# io-board-b-3.net
KiCad netlist of a schematic drawn in EAGLE
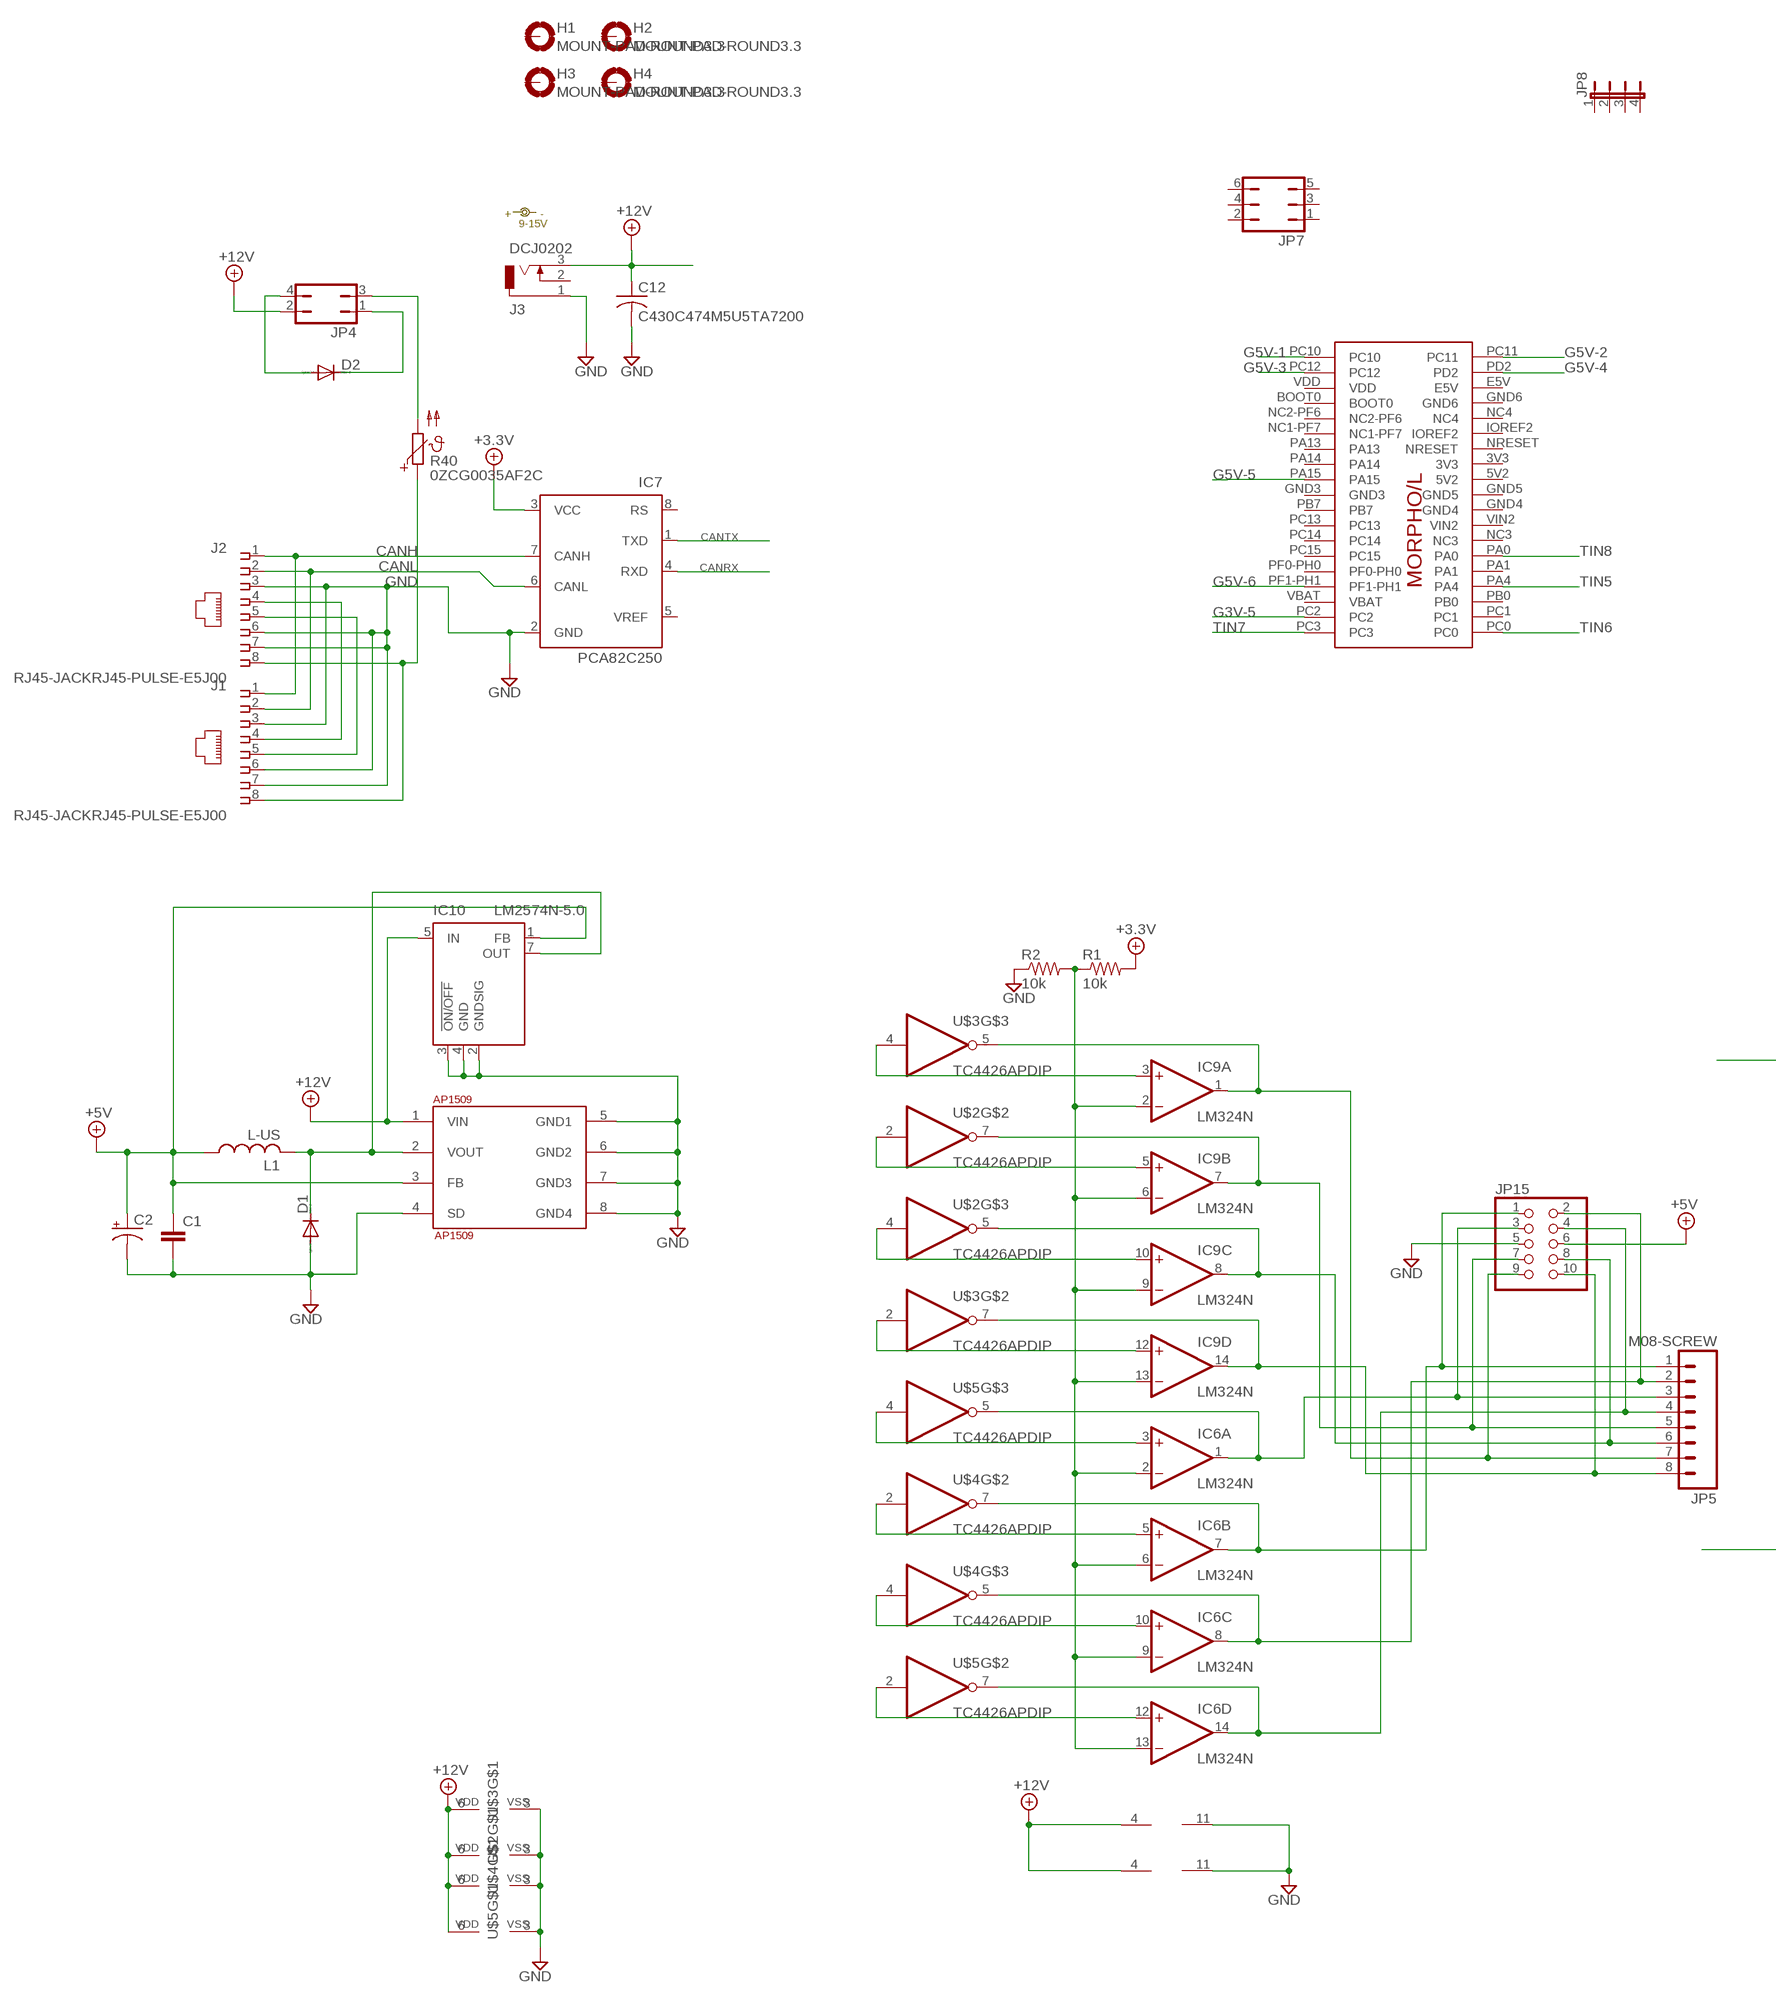
[diagram p0: schematic, sheet 1, part 1 of 2]
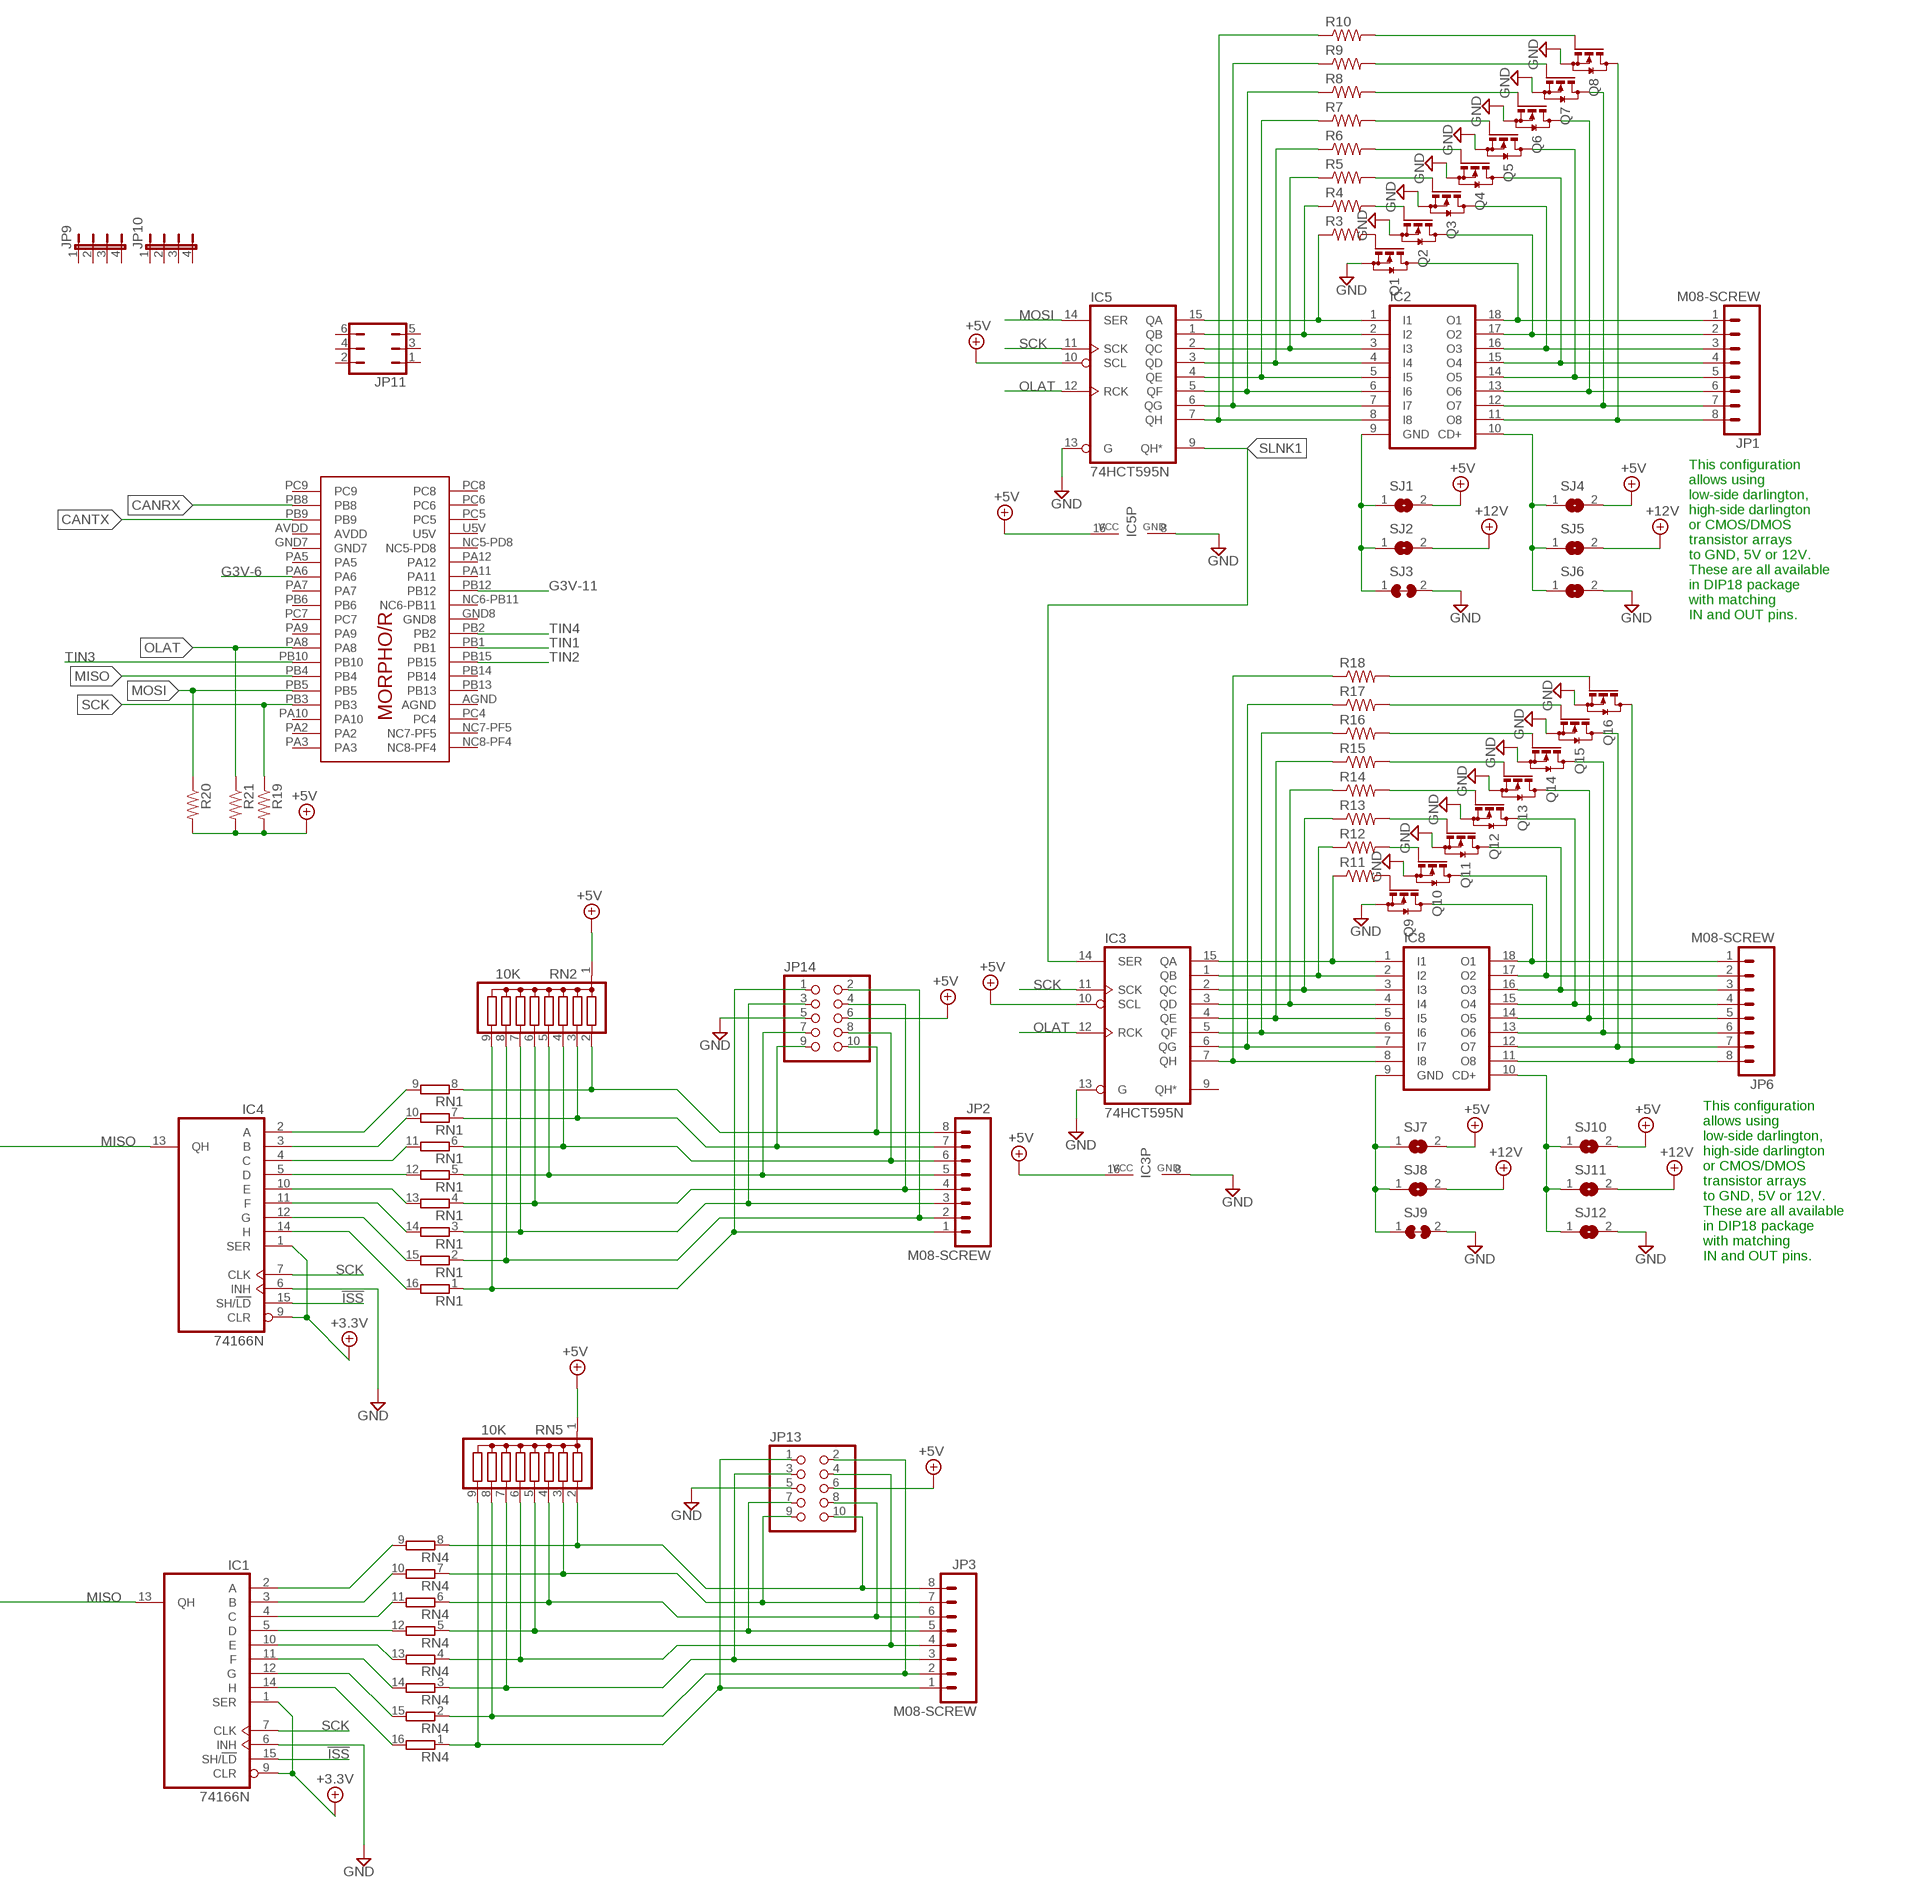
[diagram p1: schematic, sheet 1, part 2 of 2]

(export (version "E")
  (design (tool "Eeschema 10.0.6"))
  (components
    (comp (ref "+12V")
      (value "9-15V")
      (footprint "eagle-import:POWER_USAGE")
      (libsource (lib "eagle-import") (part "DOC-POWER_LABEL"))
    )
    (comp (ref "AP1509")
      (value "AP1509")
      (footprint "eagle-import:SO-08")
      (libsource (lib "eagle-import") (part "AP1509"))
    )
    (comp (ref "C1")
      (value "C-EUC1206")
      (footprint "eagle-import:C1206")
      (libsource (lib "eagle-import") (part "C-EUC1206"))
    )
    (comp (ref "C2")
      (value "CPOL-USE2.5-5")
      (footprint "eagle-import:E2,5-5")
      (libsource (lib "eagle-import") (part "CPOL-USE2.5-5"))
    )
    (comp (ref "C12")
      (value "C430C474M5U5TA7200")
      (footprint "eagle-import:C075-032X103")
      (libsource (lib "eagle-import") (part "C-US075-032X103"))
    )
    (comp (ref "D1")
      (value "DIODE-DO41-7.6")
      (footprint "eagle-import:DO41-7.6")
      (libsource (lib "eagle-import") (part "DIODE-DO41-7.6"))
    )
    (comp (ref "D2")
      (value "DIODE-DO41-7.6")
      (footprint "eagle-import:DO41-7.6")
      (libsource (lib "eagle-import") (part "DIODE-DO41-7.6"))
    )
    (comp (ref "H1")
      (value "MOUNT-PAD-ROUND3.3")
      (footprint "eagle-import:3,3-PAD")
      (libsource (lib "eagle-import") (part "MOUNT-PAD-ROUND3.3"))
    )
    (comp (ref "H2")
      (value "MOUNT-PAD-ROUND3.3")
      (footprint "eagle-import:3,3-PAD")
      (libsource (lib "eagle-import") (part "MOUNT-PAD-ROUND3.3"))
    )
    (comp (ref "H3")
      (value "MOUNT-PAD-ROUND3.3")
      (footprint "eagle-import:3,3-PAD")
      (libsource (lib "eagle-import") (part "MOUNT-PAD-ROUND3.3"))
    )
    (comp (ref "H4")
      (value "MOUNT-PAD-ROUND3.3")
      (footprint "eagle-import:3,3-PAD")
      (libsource (lib "eagle-import") (part "MOUNT-PAD-ROUND3.3"))
    )
    (comp (ref "IC1")
      (value "74166N")
      (footprint "eagle-import:DIL16")
      (libsource (lib "eagle-import") (part "74166N"))
    )
    (comp (ref "IC2")
      (value "ULN2803A")
      (footprint "eagle-import:DIL18-THIN")
      (libsource (lib "eagle-import") (part "ULN2803A"))
    )
    (comp (ref "IC3")
      (value "74HCT595N")
      (footprint "eagle-import:DIL16")
      (libsource (lib "eagle-import") (part "74595NHCT"))
    )
    (comp (ref "IC4")
      (value "74166N")
      (footprint "eagle-import:DIL16")
      (libsource (lib "eagle-import") (part "74166N"))
    )
    (comp (ref "IC5")
      (value "74HCT595N")
      (footprint "eagle-import:DIL16")
      (libsource (lib "eagle-import") (part "74595NHCT"))
    )
    (comp (ref "IC6")
      (value "LM324N")
      (footprint "eagle-import:DIL14")
      (libsource (lib "eagle-import") (part "LM324N"))
    )
    (comp (ref "IC7")
      (value "PCA82C250")
      (footprint "eagle-import:DIL08")
      (libsource (lib "eagle-import") (part "PCA82C250"))
    )
    (comp (ref "IC8")
      (value "ULN2803A")
      (footprint "eagle-import:DIL18-THIN")
      (libsource (lib "eagle-import") (part "ULN2803A"))
    )
    (comp (ref "IC9")
      (value "LM324N")
      (footprint "eagle-import:DIL14")
      (libsource (lib "eagle-import") (part "LM324N"))
    )
    (comp (ref "IC10")
      (value "LM2574N-5.0")
      (footprint "eagle-import:DIL08")
      (libsource (lib "eagle-import") (part "LM2574?-N5.0"))
    )
    (comp (ref "J1")
      (value "RJ45-JACKRJ45-PULSE-E5J00")
      (footprint "eagle-import:RJ45-PULSE-E5J88")
      (libsource (lib "eagle-import") (part "RJ45-JACKRJ45-PULSE-E5J00"))
    )
    (comp (ref "J2")
      (value "RJ45-JACKRJ45-PULSE-E5J00")
      (footprint "eagle-import:RJ45-PULSE-E5J88")
      (libsource (lib "eagle-import") (part "RJ45-JACKRJ45-PULSE-E5J00"))
    )
    (comp (ref "J3")
      (value "DCJ0202")
      (footprint "eagle-import:DCJ0202")
      (libsource (lib "eagle-import") (part "DCJ0202"))
    )
    (comp (ref "JP1")
      (value "M08-SCREW")
      (footprint "eagle-import:1X08_TERMINAL")
      (libsource (lib "eagle-import") (part "M08-SCREW"))
    )
    (comp (ref "JP2")
      (value "M08-SCREW")
      (footprint "eagle-import:1X08_TERMINAL")
      (libsource (lib "eagle-import") (part "M08-SCREW"))
    )
    (comp (ref "JP3")
      (value "M08-SCREW")
      (footprint "eagle-import:1X08_TERMINAL")
      (libsource (lib "eagle-import") (part "M08-SCREW"))
    )
    (comp (ref "JP4")
      (value "JP2Q")
      (footprint "eagle-import:JP2Q")
      (libsource (lib "eagle-import") (part "JP2Q"))
    )
    (comp (ref "JP5")
      (value "M08-SCREW")
      (footprint "eagle-import:1X08_TERMINAL")
      (libsource (lib "eagle-import") (part "M08-SCREW"))
    )
    (comp (ref "JP6")
      (value "M08-SCREW")
      (footprint "eagle-import:1X08_TERMINAL")
      (libsource (lib "eagle-import") (part "M08-SCREW"))
    )
    (comp (ref "JP7")
      (value "JP3Q")
      (footprint "eagle-import:JP3Q")
      (libsource (lib "eagle-import") (part "JP3Q"))
    )
    (comp (ref "JP8")
      (value "JP4-FLAT")
      (footprint "eagle-import:JP4F")
      (libsource (lib "eagle-import") (part "JP4-FLAT"))
    )
    (comp (ref "JP9")
      (value "JP4-FLAT")
      (footprint "eagle-import:JP4F")
      (libsource (lib "eagle-import") (part "JP4-FLAT"))
    )
    (comp (ref "JP10")
      (value "JP4-FLAT")
      (footprint "eagle-import:JP4F")
      (libsource (lib "eagle-import") (part "JP4-FLAT"))
    )
    (comp (ref "JP11")
      (value "JP3Q")
      (footprint "eagle-import:JP3Q")
      (libsource (lib "eagle-import") (part "JP3Q"))
    )
    (comp (ref "JP13")
      (value "PINHD-2X5CN")
      (footprint "eagle-import:CON10M")
      (libsource (lib "eagle-import") (part "PINHD-2X5CN"))
    )
    (comp (ref "JP14")
      (value "PINHD-2X5CN")
      (footprint "eagle-import:CON10M")
      (libsource (lib "eagle-import") (part "PINHD-2X5CN"))
    )
    (comp (ref "JP15")
      (value "PINHD-2X5CN")
      (footprint "eagle-import:CON10M")
      (libsource (lib "eagle-import") (part "PINHD-2X5CN"))
    )
    (comp (ref "L1")
      (value "L-US")
      (footprint "eagle-import:L5-8,5")
      (libsource (lib "eagle-import") (part "L-US"))
    )
    (comp (ref "Q1")
      (value "BSS123")
      (footprint "eagle-import:SOT23")
      (libsource (lib "eagle-import") (part "BSS123"))
    )
    (comp (ref "Q2")
      (value "BSS123")
      (footprint "eagle-import:SOT23")
      (libsource (lib "eagle-import") (part "BSS123"))
    )
    (comp (ref "Q3")
      (value "BSS123")
      (footprint "eagle-import:SOT23")
      (libsource (lib "eagle-import") (part "BSS123"))
    )
    (comp (ref "Q4")
      (value "BSS123")
      (footprint "eagle-import:SOT23")
      (libsource (lib "eagle-import") (part "BSS123"))
    )
    (comp (ref "Q5")
      (value "BSS123")
      (footprint "eagle-import:SOT23")
      (libsource (lib "eagle-import") (part "BSS123"))
    )
    (comp (ref "Q6")
      (value "BSS123")
      (footprint "eagle-import:SOT23")
      (libsource (lib "eagle-import") (part "BSS123"))
    )
    (comp (ref "Q7")
      (value "BSS123")
      (footprint "eagle-import:SOT23")
      (libsource (lib "eagle-import") (part "BSS123"))
    )
    (comp (ref "Q8")
      (value "BSS123")
      (footprint "eagle-import:SOT23")
      (libsource (lib "eagle-import") (part "BSS123"))
    )
    (comp (ref "Q9")
      (value "BSS123")
      (footprint "eagle-import:SOT23")
      (libsource (lib "eagle-import") (part "BSS123"))
    )
    (comp (ref "Q10")
      (value "BSS123")
      (footprint "eagle-import:SOT23")
      (libsource (lib "eagle-import") (part "BSS123"))
    )
    (comp (ref "Q11")
      (value "BSS123")
      (footprint "eagle-import:SOT23")
      (libsource (lib "eagle-import") (part "BSS123"))
    )
    (comp (ref "Q12")
      (value "BSS123")
      (footprint "eagle-import:SOT23")
      (libsource (lib "eagle-import") (part "BSS123"))
    )
    (comp (ref "Q13")
      (value "BSS123")
      (footprint "eagle-import:SOT23")
      (libsource (lib "eagle-import") (part "BSS123"))
    )
    (comp (ref "Q14")
      (value "BSS123")
      (footprint "eagle-import:SOT23")
      (libsource (lib "eagle-import") (part "BSS123"))
    )
    (comp (ref "Q15")
      (value "BSS123")
      (footprint "eagle-import:SOT23")
      (libsource (lib "eagle-import") (part "BSS123"))
    )
    (comp (ref "Q16")
      (value "BSS123")
      (footprint "eagle-import:SOT23")
      (libsource (lib "eagle-import") (part "BSS123"))
    )
    (comp (ref "R1")
      (value "10k")
      (footprint "eagle-import:R1206")
      (libsource (lib "eagle-import") (part "R-US_R1206"))
    )
    (comp (ref "R2")
      (value "10k")
      (footprint "eagle-import:R1206")
      (libsource (lib "eagle-import") (part "R-US_R1206"))
    )
    (comp (ref "R3")
      (value "R-US_R0603")
      (footprint "eagle-import:R0603")
      (libsource (lib "eagle-import") (part "R-US_R0603"))
    )
    (comp (ref "R4")
      (value "R-US_R0603")
      (footprint "eagle-import:R0603")
      (libsource (lib "eagle-import") (part "R-US_R0603"))
    )
    (comp (ref "R5")
      (value "R-US_R0603")
      (footprint "eagle-import:R0603")
      (libsource (lib "eagle-import") (part "R-US_R0603"))
    )
    (comp (ref "R6")
      (value "R-US_R0603")
      (footprint "eagle-import:R0603")
      (libsource (lib "eagle-import") (part "R-US_R0603"))
    )
    (comp (ref "R7")
      (value "R-US_R0603")
      (footprint "eagle-import:R0603")
      (libsource (lib "eagle-import") (part "R-US_R0603"))
    )
    (comp (ref "R8")
      (value "R-US_R0603")
      (footprint "eagle-import:R0603")
      (libsource (lib "eagle-import") (part "R-US_R0603"))
    )
    (comp (ref "R9")
      (value "R-US_R0603")
      (footprint "eagle-import:R0603")
      (libsource (lib "eagle-import") (part "R-US_R0603"))
    )
    (comp (ref "R10")
      (value "R-US_R0603")
      (footprint "eagle-import:R0603")
      (libsource (lib "eagle-import") (part "R-US_R0603"))
    )
    (comp (ref "R11")
      (value "R-US_R0603")
      (footprint "eagle-import:R0603")
      (libsource (lib "eagle-import") (part "R-US_R0603"))
    )
    (comp (ref "R12")
      (value "R-US_R0603")
      (footprint "eagle-import:R0603")
      (libsource (lib "eagle-import") (part "R-US_R0603"))
    )
    (comp (ref "R13")
      (value "R-US_R0603")
      (footprint "eagle-import:R0603")
      (libsource (lib "eagle-import") (part "R-US_R0603"))
    )
    (comp (ref "R14")
      (value "R-US_R0603")
      (footprint "eagle-import:R0603")
      (libsource (lib "eagle-import") (part "R-US_R0603"))
    )
    (comp (ref "R15")
      (value "R-US_R0603")
      (footprint "eagle-import:R0603")
      (libsource (lib "eagle-import") (part "R-US_R0603"))
    )
    (comp (ref "R16")
      (value "R-US_R0603")
      (footprint "eagle-import:R0603")
      (libsource (lib "eagle-import") (part "R-US_R0603"))
    )
    (comp (ref "R17")
      (value "R-US_R0603")
      (footprint "eagle-import:R0603")
      (libsource (lib "eagle-import") (part "R-US_R0603"))
    )
    (comp (ref "R18")
      (value "R-US_R0603")
      (footprint "eagle-import:R0603")
      (libsource (lib "eagle-import") (part "R-US_R0603"))
    )
    (comp (ref "R19")
      (value "R-US_R0805")
      (footprint "eagle-import:R0805")
      (libsource (lib "eagle-import") (part "rcl_334_R-US_R0805"))
    )
    (comp (ref "R20")
      (value "R-US_R0805")
      (footprint "eagle-import:R0805")
      (libsource (lib "eagle-import") (part "rcl_334_R-US_R0805"))
    )
    (comp (ref "R21")
      (value "R-US_R0805")
      (footprint "eagle-import:R0805")
      (libsource (lib "eagle-import") (part "rcl_334_R-US_R0805"))
    )
    (comp (ref "R40")
      (value "0ZCG0035AF2C")
      (footprint "eagle-import:PTC1812")
      (libsource (lib "eagle-import") (part "PTC_1812"))
    )
    (comp (ref "RN1")
      (value "8R-P")
      (footprint "eagle-import:DIL16")
      (libsource (lib "eagle-import") (part "8R-P"))
    )
    (comp (ref "RN2")
      (value "10K")
      (footprint "eagle-import:SIL9")
      (libsource (lib "eagle-import") (part "G08R"))
    )
    (comp (ref "RN4")
      (value "8R-P")
      (footprint "eagle-import:DIL16")
      (libsource (lib "eagle-import") (part "8R-P"))
    )
    (comp (ref "RN5")
      (value "10K")
      (footprint "eagle-import:SIL9")
      (libsource (lib "eagle-import") (part "G08R"))
    )
    (comp (ref "SJ1")
      (value "SJ")
      (footprint "eagle-import:SJ-RND")
      (libsource (lib "eagle-import") (part "SJ"))
    )
    (comp (ref "SJ2")
      (value "SJ")
      (footprint "eagle-import:SJ-RND")
      (libsource (lib "eagle-import") (part "SJ"))
    )
    (comp (ref "SJ3")
      (value "SJ-C")
      (footprint "eagle-import:SJW-C")
      (libsource (lib "eagle-import") (part "SJ-C"))
    )
    (comp (ref "SJ4")
      (value "SJ")
      (footprint "eagle-import:SJ-RND")
      (libsource (lib "eagle-import") (part "SJ"))
    )
    (comp (ref "SJ5")
      (value "SJ")
      (footprint "eagle-import:SJ-RND")
      (libsource (lib "eagle-import") (part "SJ"))
    )
    (comp (ref "SJ6")
      (value "SJ")
      (footprint "eagle-import:SJ-RND")
      (libsource (lib "eagle-import") (part "SJ"))
    )
    (comp (ref "SJ7")
      (value "SJ")
      (footprint "eagle-import:SJ-RND")
      (libsource (lib "eagle-import") (part "SJ"))
    )
    (comp (ref "SJ8")
      (value "SJ")
      (footprint "eagle-import:SJ-RND")
      (libsource (lib "eagle-import") (part "SJ"))
    )
    (comp (ref "SJ9")
      (value "SJ-C")
      (footprint "eagle-import:SJW-C")
      (libsource (lib "eagle-import") (part "SJ-C"))
    )
    (comp (ref "SJ10")
      (value "SJ")
      (footprint "eagle-import:SJ-RND")
      (libsource (lib "eagle-import") (part "SJ"))
    )
    (comp (ref "SJ11")
      (value "SJ")
      (footprint "eagle-import:SJ-RND")
      (libsource (lib "eagle-import") (part "SJ"))
    )
    (comp (ref "SJ12")
      (value "SJ")
      (footprint "eagle-import:SJ-RND")
      (libsource (lib "eagle-import") (part "SJ"))
    )
    (comp (ref "U$1")
      (value "NUCLEO_64_GENERIC")
      (footprint "eagle-import:NUCLEO_BRD_BASE64")
      (libsource (lib "eagle-import") (part "NUCLEO_64_GENERIC"))
    )
    (comp (ref "U$2")
      (value "TC4426APDIP")
      (footprint "eagle-import:DIL08-LONG")
      (libsource (lib "eagle-import") (part "TC4426APDIP"))
    )
    (comp (ref "U$3")
      (value "TC4426APDIP")
      (footprint "eagle-import:DIL08-LONG")
      (libsource (lib "eagle-import") (part "TC4426APDIP"))
    )
    (comp (ref "U$4")
      (value "TC4426APDIP")
      (footprint "eagle-import:DIL08-LONG")
      (libsource (lib "eagle-import") (part "TC4426APDIP"))
    )
    (comp (ref "U$5")
      (value "TC4426APDIP")
      (footprint "eagle-import:DIL08-LONG")
      (libsource (lib "eagle-import") (part "TC4426APDIP"))
    )
  )
  (nets
    (net (code "1") (name "+3.3V") (class "Default")
      (node (ref "IC1") (pin "1") (pinfunction "SER_1") (pintype "input"))
      (node (ref "IC1") (pin "9") (pinfunction "CLR_9") (pintype "input"))
      (node (ref "IC4") (pin "1") (pinfunction "SER_1") (pintype "input"))
      (node (ref "IC4") (pin "9") (pinfunction "CLR_9") (pintype "input"))
      (node (ref "IC7") (pin "3") (pinfunction "VCC_3") (pintype "power_in"))
      (node (ref "R1") (pin "2") (pinfunction "2_2") (pintype "passive"))
    )
    (net (code "2") (name "+5V") (class "Default")
      (node (ref "AP1509") (pin "3") (pinfunction "FB_3") (pintype "bidirectional"))
      (node (ref "C1") (pin "1") (pinfunction "1_1") (pintype "passive"))
      (node (ref "C2") (pin "+") (pinfunction "+_+") (pintype "passive"))
      (node (ref "IC10") (pin "1") (pinfunction "FB_1") (pintype "input"))
      (node (ref "IC3") (pin "10") (pinfunction "SCL_10") (pintype "input"))
      (node (ref "IC3") (pin "16") (pinfunction "VCC_16") (pintype "power_in"))
      (node (ref "IC5") (pin "10") (pinfunction "SCL_10") (pintype "input"))
      (node (ref "IC5") (pin "16") (pinfunction "VCC_16") (pintype "power_in"))
      (node (ref "JP13") (pin "6") (pinfunction "6_6") (pintype "passive"))
      (node (ref "JP14") (pin "6") (pinfunction "6_6") (pintype "passive"))
      (node (ref "JP15") (pin "6") (pinfunction "6_6") (pintype "passive"))
      (node (ref "L1") (pin "1") (pinfunction "1_1") (pintype "passive"))
      (node (ref "R19") (pin "2") (pinfunction "2_2") (pintype "passive"))
      (node (ref "R20") (pin "2") (pinfunction "2_2") (pintype "passive"))
      (node (ref "R21") (pin "2") (pinfunction "2_2") (pintype "passive"))
      (node (ref "RN2") (pin "1") (pinfunction "1_1") (pintype "passive"))
      (node (ref "RN5") (pin "1") (pinfunction "1_1") (pintype "passive"))
      (node (ref "SJ1") (pin "2") (pinfunction "2_2") (pintype "passive"))
      (node (ref "SJ10") (pin "2") (pinfunction "2_2") (pintype "passive"))
      (node (ref "SJ4") (pin "2") (pinfunction "2_2") (pintype "passive"))
      (node (ref "SJ7") (pin "2") (pinfunction "2_2") (pintype "passive"))
    )
    (net (code "3") (name "+12V") (class "Default")
      (node (ref "AP1509") (pin "1") (pinfunction "VIN_1") (pintype "bidirectional"))
      (node (ref "C12") (pin "1") (pinfunction "1_1") (pintype "passive"))
      (node (ref "IC10") (pin "5") (pinfunction "IN_5") (pintype "input"))
      (node (ref "IC6") (pin "4") (pinfunction "V+_4") (pintype "power_in"))
      (node (ref "IC9") (pin "4") (pinfunction "V+_4") (pintype "power_in"))
      (node (ref "J3") (pin "3") (pinfunction "3_3") (pintype "passive"))
      (node (ref "JP4") (pin "2") (pinfunction "2_2") (pintype "passive"))
      (node (ref "SJ11") (pin "2") (pinfunction "2_2") (pintype "passive"))
      (node (ref "SJ2") (pin "2") (pinfunction "2_2") (pintype "passive"))
      (node (ref "SJ5") (pin "2") (pinfunction "2_2") (pintype "passive"))
      (node (ref "SJ8") (pin "2") (pinfunction "2_2") (pintype "passive"))
      (node (ref "U$2") (pin "6") (pinfunction "VDD_6") (pintype "power_in"))
      (node (ref "U$3") (pin "6") (pinfunction "VDD_6") (pintype "power_in"))
      (node (ref "U$4") (pin "6") (pinfunction "VDD_6") (pintype "power_in"))
      (node (ref "U$5") (pin "6") (pinfunction "VDD_6") (pintype "power_in"))
    )
    (net (code "4") (name "/3V3") (class "Default")
      (node (ref "U$1") (pin "3V3") (pinfunction "3V3_3V3") (pintype "power_in"))
    )
    (net (code "5") (name "/5V2") (class "Default")
      (node (ref "U$1") (pin "5V2") (pinfunction "5V2_5V2") (pintype "power_in"))
    )
    (net (code "6") (name "/AGND") (class "Default")
      (node (ref "U$1") (pin "AGND") (pinfunction "AGND_AGND") (pintype "power_in"))
    )
    (net (code "7") (name "/AVDD") (class "Default")
      (node (ref "U$1") (pin "AVDD") (pinfunction "AVDD_AVDD") (pintype "power_in"))
    )
    (net (code "8") (name "/CANH") (class "Default")
      (node (ref "IC7") (pin "7") (pinfunction "CANH_7") (pintype "bidirectional"))
      (node (ref "J1") (pin "1") (pinfunction "1_1") (pintype "passive"))
      (node (ref "J2") (pin "1") (pinfunction "1_1") (pintype "passive"))
    )
    (net (code "9") (name "/CANL") (class "Default")
      (node (ref "IC7") (pin "6") (pinfunction "CANL_6") (pintype "bidirectional"))
      (node (ref "J1") (pin "2") (pinfunction "2_2") (pintype "passive"))
      (node (ref "J2") (pin "2") (pinfunction "2_2") (pintype "passive"))
    )
    (net (code "10") (name "/E5V") (class "Default")
      (node (ref "U$1") (pin "E5V") (pinfunction "E5V_E5V") (pintype "power_in"))
    )
    (net (code "11") (name "/G3V-5") (class "Default")
      (node (ref "U$1") (pin "PC2") (pinfunction "PC2_PC2") (pintype "bidirectional"))
    )
    (net (code "12") (name "/G3V-6") (class "Default")
      (node (ref "U$1") (pin "PA6") (pinfunction "PA6_PA6") (pintype "bidirectional"))
    )
    (net (code "13") (name "/G3V-11") (class "Default")
      (node (ref "U$1") (pin "PB12") (pinfunction "PB12_PB12") (pintype "bidirectional"))
    )
    (net (code "14") (name "/G5V-1") (class "Default")
      (node (ref "U$1") (pin "PC10") (pinfunction "PC10_PC10") (pintype "bidirectional"))
    )
    (net (code "15") (name "/G5V-2") (class "Default")
      (node (ref "U$1") (pin "PC11") (pinfunction "PC11_PC11") (pintype "bidirectional"))
    )
    (net (code "16") (name "/G5V-3") (class "Default")
      (node (ref "U$1") (pin "PC12") (pinfunction "PC12_PC12") (pintype "bidirectional"))
    )
    (net (code "17") (name "/G5V-4") (class "Default")
      (node (ref "U$1") (pin "PD2") (pinfunction "PD2_PD2") (pintype "bidirectional"))
    )
    (net (code "18") (name "/G5V-5") (class "Default")
      (node (ref "U$1") (pin "PA15") (pinfunction "PA15_PA15") (pintype "bidirectional"))
    )
    (net (code "19") (name "/G5V-6") (class "Default")
      (node (ref "U$1") (pin "PF1-PH1") (pinfunction "PF1-PH1_PF1-PH1") (pintype "bidirectional"))
    )
    (net (code "20") (name "/GND3") (class "Default")
      (node (ref "U$1") (pin "GND3") (pinfunction "GND3_GND3") (pintype "power_in"))
    )
    (net (code "21") (name "/GND4") (class "Default")
      (node (ref "U$1") (pin "GND4") (pinfunction "GND4_GND4") (pintype "power_in"))
    )
    (net (code "22") (name "/GND5") (class "Default")
      (node (ref "U$1") (pin "GND5") (pinfunction "GND5_GND5") (pintype "power_in"))
    )
    (net (code "23") (name "/GND6") (class "Default")
      (node (ref "U$1") (pin "GND6") (pinfunction "GND6_GND6") (pintype "power_in"))
    )
    (net (code "24") (name "/GND7") (class "Default")
      (node (ref "U$1") (pin "GND7") (pinfunction "GND7_GND7") (pintype "power_in"))
    )
    (net (code "25") (name "/GND8") (class "Default")
      (node (ref "U$1") (pin "GND8") (pinfunction "GND8_GND8") (pintype "power_in"))
    )
    (net (code "26") (name "/TIN1") (class "Default")
      (node (ref "IC9") (pin "3") (pinfunction "+IN_3") (pintype "input"))
      (node (ref "U$1") (pin "PB1") (pinfunction "PB1_PB1") (pintype "bidirectional"))
      (node (ref "U$3") (pin "4") (pinfunction "I_4") (pintype "input"))
    )
    (net (code "27") (name "/TIN2") (class "Default")
      (node (ref "IC9") (pin "5") (pinfunction "+IN_5") (pintype "input"))
      (node (ref "U$1") (pin "PB15") (pinfunction "PB15_PB15") (pintype "bidirectional"))
      (node (ref "U$2") (pin "2") (pinfunction "I_2") (pintype "input"))
    )
    (net (code "28") (name "/TIN3") (class "Default")
      (node (ref "IC9") (pin "10") (pinfunction "+IN_10") (pintype "input"))
      (node (ref "U$1") (pin "PB10") (pinfunction "PB10_PB10") (pintype "bidirectional"))
      (node (ref "U$2") (pin "4") (pinfunction "I_4") (pintype "input"))
    )
    (net (code "29") (name "/TIN4") (class "Default")
      (node (ref "IC9") (pin "12") (pinfunction "+IN_12") (pintype "input"))
      (node (ref "U$1") (pin "PB2") (pinfunction "PB2_PB2") (pintype "bidirectional"))
      (node (ref "U$3") (pin "2") (pinfunction "I_2") (pintype "input"))
    )
    (net (code "30") (name "/TIN5") (class "Default")
      (node (ref "IC6") (pin "3") (pinfunction "+IN_3") (pintype "input"))
      (node (ref "U$1") (pin "PA4") (pinfunction "PA4_PA4") (pintype "bidirectional"))
      (node (ref "U$5") (pin "4") (pinfunction "I_4") (pintype "input"))
    )
    (net (code "31") (name "/TIN6") (class "Default")
      (node (ref "IC6") (pin "5") (pinfunction "+IN_5") (pintype "input"))
      (node (ref "U$1") (pin "PC0") (pinfunction "PC0_PC0") (pintype "bidirectional"))
      (node (ref "U$4") (pin "2") (pinfunction "I_2") (pintype "input"))
    )
    (net (code "32") (name "/TIN7") (class "Default")
      (node (ref "IC6") (pin "10") (pinfunction "+IN_10") (pintype "input"))
      (node (ref "U$1") (pin "PC3") (pinfunction "PC3_PC3") (pintype "bidirectional"))
      (node (ref "U$4") (pin "4") (pinfunction "I_4") (pintype "input"))
    )
    (net (code "33") (name "/TIN8") (class "Default")
      (node (ref "IC6") (pin "12") (pinfunction "+IN_12") (pintype "input"))
      (node (ref "U$1") (pin "PA0") (pinfunction "PA0_PA0") (pintype "bidirectional"))
      (node (ref "U$5") (pin "2") (pinfunction "I_2") (pintype "input"))
    )
    (net (code "34") (name "/U5V") (class "Default")
      (node (ref "U$1") (pin "U5V") (pinfunction "U5V_U5V") (pintype "power_in"))
    )
    (net (code "35") (name "/VBAT") (class "Default")
      (node (ref "U$1") (pin "VBAT") (pinfunction "VBAT_VBAT") (pintype "power_in"))
    )
    (net (code "36") (name "/VDD") (class "Default")
      (node (ref "U$1") (pin "VDD") (pinfunction "VDD_VDD") (pintype "power_in"))
    )
    (net (code "37") (name "/VIN2") (class "Default")
      (node (ref "U$1") (pin "VIN2") (pinfunction "VIN2_VIN2") (pintype "power_in"))
    )
    (net (code "38") (name "/~{ISS}") (class "Default")
      (node (ref "IC1") (pin "15") (pinfunction "SH/~{LD}_15") (pintype "input"))
      (node (ref "IC4") (pin "15") (pinfunction "SH/~{LD}_15") (pintype "input"))
    )
    (net (code "39") (name "CANRX") (class "Default")
      (node (ref "IC7") (pin "4") (pinfunction "RXD_4") (pintype "output"))
      (node (ref "U$1") (pin "PB8") (pinfunction "PB8_PB8") (pintype "bidirectional"))
    )
    (net (code "40") (name "CANTX") (class "Default")
      (node (ref "IC7") (pin "1") (pinfunction "TXD_1") (pintype "input"))
      (node (ref "U$1") (pin "PB9") (pinfunction "PB9_PB9") (pintype "bidirectional"))
    )
    (net (code "41") (name "GND") (class "Default")
      (node (ref "AP1509") (pin "4") (pinfunction "SD_4") (pintype "bidirectional"))
      (node (ref "AP1509") (pin "5") (pinfunction "GND1_5") (pintype "power_in"))
      (node (ref "AP1509") (pin "6") (pinfunction "GND2_6") (pintype "power_in"))
      (node (ref "AP1509") (pin "7") (pinfunction "GND3_7") (pintype "power_in"))
      (node (ref "AP1509") (pin "8") (pinfunction "GND4_8") (pintype "power_in"))
      (node (ref "C1") (pin "2") (pinfunction "2_2") (pintype "passive"))
      (node (ref "C12") (pin "2") (pinfunction "2_2") (pintype "passive"))
      (node (ref "C2") (pin "-") (pinfunction "-_-") (pintype "passive"))
      (node (ref "D1") (pin "A") (pinfunction "A_A") (pintype "passive"))
      (node (ref "IC1") (pin "6") (pinfunction "INH_6") (pintype "input"))
      (node (ref "IC10") (pin "2") (pinfunction "GNDSIG_2") (pintype "input"))
      (node (ref "IC10") (pin "3") (pinfunction "~{ON/OFF}_3") (pintype "input"))
      (node (ref "IC10") (pin "4") (pinfunction "GND_4") (pintype "power_in"))
      (node (ref "IC3") (pin "13") (pinfunction "G_13") (pintype "input"))
      (node (ref "IC3") (pin "8") (pinfunction "GND_8") (pintype "power_in"))
      (node (ref "IC4") (pin "6") (pinfunction "INH_6") (pintype "input"))
      (node (ref "IC5") (pin "13") (pinfunction "G_13") (pintype "input"))
      (node (ref "IC5") (pin "8") (pinfunction "GND_8") (pintype "power_in"))
      (node (ref "IC6") (pin "11") (pinfunction "V-_11") (pintype "power_in"))
      (node (ref "IC7") (pin "2") (pinfunction "GND_2") (pintype "power_in"))
      (node (ref "IC9") (pin "11") (pinfunction "V-_11") (pintype "power_in"))
      (node (ref "J1") (pin "3") (pinfunction "3_3") (pintype "passive"))
      (node (ref "J1") (pin "6") (pinfunction "6_6") (pintype "passive"))
      (node (ref "J1") (pin "7") (pinfunction "7_7") (pintype "passive"))
      (node (ref "J2") (pin "3") (pinfunction "3_3") (pintype "passive"))
      (node (ref "J2") (pin "6") (pinfunction "6_6") (pintype "passive"))
      (node (ref "J2") (pin "7") (pinfunction "7_7") (pintype "passive"))
      (node (ref "J3") (pin "1") (pinfunction "1_1") (pintype "passive"))
      (node (ref "JP13") (pin "5") (pinfunction "5_5") (pintype "passive"))
      (node (ref "JP14") (pin "5") (pinfunction "5_5") (pintype "passive"))
      (node (ref "JP15") (pin "5") (pinfunction "5_5") (pintype "passive"))
      (node (ref "Q1") (pin "2") (pinfunction "S_2") (pintype "passive"))
      (node (ref "Q10") (pin "2") (pinfunction "S_2") (pintype "passive"))
      (node (ref "Q11") (pin "2") (pinfunction "S_2") (pintype "passive"))
      (node (ref "Q12") (pin "2") (pinfunction "S_2") (pintype "passive"))
      (node (ref "Q13") (pin "2") (pinfunction "S_2") (pintype "passive"))
      (node (ref "Q14") (pin "2") (pinfunction "S_2") (pintype "passive"))
      (node (ref "Q15") (pin "2") (pinfunction "S_2") (pintype "passive"))
      (node (ref "Q16") (pin "2") (pinfunction "S_2") (pintype "passive"))
      (node (ref "Q2") (pin "2") (pinfunction "S_2") (pintype "passive"))
      (node (ref "Q3") (pin "2") (pinfunction "S_2") (pintype "passive"))
      (node (ref "Q4") (pin "2") (pinfunction "S_2") (pintype "passive"))
      (node (ref "Q5") (pin "2") (pinfunction "S_2") (pintype "passive"))
      (node (ref "Q6") (pin "2") (pinfunction "S_2") (pintype "passive"))
      (node (ref "Q7") (pin "2") (pinfunction "S_2") (pintype "passive"))
      (node (ref "Q8") (pin "2") (pinfunction "S_2") (pintype "passive"))
      (node (ref "Q9") (pin "2") (pinfunction "S_2") (pintype "passive"))
      (node (ref "R2") (pin "1") (pinfunction "1_1") (pintype "passive"))
      (node (ref "SJ12") (pin "2") (pinfunction "2_2") (pintype "passive"))
      (node (ref "SJ3") (pin "2") (pinfunction "2_2") (pintype "passive"))
      (node (ref "SJ6") (pin "2") (pinfunction "2_2") (pintype "passive"))
      (node (ref "SJ9") (pin "2") (pinfunction "2_2") (pintype "passive"))
      (node (ref "U$2") (pin "3") (pinfunction "VSS_3") (pintype "power_in"))
      (node (ref "U$3") (pin "3") (pinfunction "VSS_3") (pintype "power_in"))
      (node (ref "U$4") (pin "3") (pinfunction "VSS_3") (pintype "power_in"))
      (node (ref "U$5") (pin "3") (pinfunction "VSS_3") (pintype "power_in"))
    )
    (net (code "42") (name "MISO") (class "Default")
      (node (ref "IC1") (pin "13") (pinfunction "QH_13") (pintype "output"))
      (node (ref "IC4") (pin "13") (pinfunction "QH_13") (pintype "output"))
      (node (ref "U$1") (pin "PB4") (pinfunction "PB4_PB4") (pintype "bidirectional"))
    )
    (net (code "43") (name "MOSI") (class "Default")
      (node (ref "IC5") (pin "14") (pinfunction "SER_14") (pintype "input"))
      (node (ref "R20") (pin "1") (pinfunction "1_1") (pintype "passive"))
      (node (ref "U$1") (pin "PB5") (pinfunction "PB5_PB5") (pintype "bidirectional"))
    )
    (net (code "44") (name "Net-(AP1509-VOUT)") (class "Default")
      (node (ref "AP1509") (pin "2") (pinfunction "VOUT_2") (pintype "bidirectional"))
      (node (ref "D1") (pin "C") (pinfunction "C_C") (pintype "passive"))
      (node (ref "IC10") (pin "7") (pinfunction "OUT_7") (pintype "passive"))
      (node (ref "L1") (pin "2") (pinfunction "2_2") (pintype "passive"))
    )
    (net (code "45") (name "Net-(D2-PadA)") (class "Default")
      (node (ref "D2") (pin "A") (pinfunction "A_A") (pintype "passive"))
      (node (ref "JP4") (pin "4") (pinfunction "4_4") (pintype "passive"))
    )
    (net (code "46") (name "Net-(D2-PadC)") (class "Default")
      (node (ref "D2") (pin "C") (pinfunction "C_C") (pintype "passive"))
      (node (ref "JP4") (pin "1") (pinfunction "1_1") (pintype "passive"))
    )
    (net (code "47") (name "Net-(IC1A-A)") (class "Default")
      (node (ref "IC1") (pin "2") (pinfunction "A_2") (pintype "input"))
      (node (ref "RN4") (pin "9") (pinfunction "2_9") (pintype "passive"))
    )
    (net (code "48") (name "Net-(IC1A-B)") (class "Default")
      (node (ref "IC1") (pin "3") (pinfunction "B_3") (pintype "input"))
      (node (ref "RN4") (pin "10") (pinfunction "2_10") (pintype "passive"))
    )
    (net (code "49") (name "Net-(IC1A-C)") (class "Default")
      (node (ref "IC1") (pin "4") (pinfunction "C_4") (pintype "input"))
      (node (ref "RN4") (pin "11") (pinfunction "2_11") (pintype "passive"))
    )
    (net (code "50") (name "Net-(IC1A-D)") (class "Default")
      (node (ref "IC1") (pin "5") (pinfunction "D_5") (pintype "input"))
      (node (ref "RN4") (pin "12") (pinfunction "2_12") (pintype "passive"))
    )
    (net (code "51") (name "Net-(IC1A-E)") (class "Default")
      (node (ref "IC1") (pin "10") (pinfunction "E_10") (pintype "input"))
      (node (ref "RN4") (pin "13") (pinfunction "2_13") (pintype "passive"))
    )
    (net (code "52") (name "Net-(IC1A-F)") (class "Default")
      (node (ref "IC1") (pin "11") (pinfunction "F_11") (pintype "input"))
      (node (ref "RN4") (pin "14") (pinfunction "2_14") (pintype "passive"))
    )
    (net (code "53") (name "Net-(IC1A-G)") (class "Default")
      (node (ref "IC1") (pin "12") (pinfunction "G_12") (pintype "input"))
      (node (ref "RN4") (pin "15") (pinfunction "2_15") (pintype "passive"))
    )
    (net (code "54") (name "Net-(IC1A-H)") (class "Default")
      (node (ref "IC1") (pin "14") (pinfunction "H_14") (pintype "input"))
      (node (ref "RN4") (pin "16") (pinfunction "2_16") (pintype "passive"))
    )
    (net (code "55") (name "Net-(IC2-CD+)") (class "Default")
      (node (ref "IC2") (pin "10") (pinfunction "CD+_10") (pintype "passive"))
      (node (ref "SJ4") (pin "1") (pinfunction "1_1") (pintype "passive"))
      (node (ref "SJ5") (pin "1") (pinfunction "1_1") (pintype "passive"))
      (node (ref "SJ6") (pin "1") (pinfunction "1_1") (pintype "passive"))
    )
    (net (code "56") (name "Net-(IC2-GND)") (class "Default")
      (node (ref "IC2") (pin "9") (pinfunction "GND_9") (pintype "power_in"))
      (node (ref "SJ1") (pin "1") (pinfunction "1_1") (pintype "passive"))
      (node (ref "SJ2") (pin "1") (pinfunction "1_1") (pintype "passive"))
      (node (ref "SJ3") (pin "1") (pinfunction "1_1") (pintype "passive"))
    )
    (net (code "57") (name "Net-(IC2-I1)") (class "Default")
      (node (ref "IC2") (pin "1") (pinfunction "I1_1") (pintype "input"))
      (node (ref "IC5") (pin "15") (pinfunction "QA_15") (pintype "tri_state"))
      (node (ref "R3") (pin "1") (pinfunction "1_1") (pintype "passive"))
    )
    (net (code "58") (name "Net-(IC2-I2)") (class "Default")
      (node (ref "IC2") (pin "2") (pinfunction "I2_2") (pintype "input"))
      (node (ref "IC5") (pin "1") (pinfunction "QB_1") (pintype "tri_state"))
      (node (ref "R4") (pin "1") (pinfunction "1_1") (pintype "passive"))
    )
    (net (code "59") (name "Net-(IC2-I3)") (class "Default")
      (node (ref "IC2") (pin "3") (pinfunction "I3_3") (pintype "input"))
      (node (ref "IC5") (pin "2") (pinfunction "QC_2") (pintype "tri_state"))
      (node (ref "R5") (pin "1") (pinfunction "1_1") (pintype "passive"))
    )
    (net (code "60") (name "Net-(IC2-I4)") (class "Default")
      (node (ref "IC2") (pin "4") (pinfunction "I4_4") (pintype "input"))
      (node (ref "IC5") (pin "3") (pinfunction "QD_3") (pintype "tri_state"))
      (node (ref "R6") (pin "1") (pinfunction "1_1") (pintype "passive"))
    )
    (net (code "61") (name "Net-(IC2-I5)") (class "Default")
      (node (ref "IC2") (pin "5") (pinfunction "I5_5") (pintype "input"))
      (node (ref "IC5") (pin "4") (pinfunction "QE_4") (pintype "tri_state"))
      (node (ref "R7") (pin "1") (pinfunction "1_1") (pintype "passive"))
    )
    (net (code "62") (name "Net-(IC2-I6)") (class "Default")
      (node (ref "IC2") (pin "6") (pinfunction "I6_6") (pintype "input"))
      (node (ref "IC5") (pin "5") (pinfunction "QF_5") (pintype "tri_state"))
      (node (ref "R8") (pin "1") (pinfunction "1_1") (pintype "passive"))
    )
    (net (code "63") (name "Net-(IC2-I7)") (class "Default")
      (node (ref "IC2") (pin "7") (pinfunction "I7_7") (pintype "input"))
      (node (ref "IC5") (pin "6") (pinfunction "QG_6") (pintype "tri_state"))
      (node (ref "R9") (pin "1") (pinfunction "1_1") (pintype "passive"))
    )
    (net (code "64") (name "Net-(IC2-I8)") (class "Default")
      (node (ref "IC2") (pin "8") (pinfunction "I8_8") (pintype "input"))
      (node (ref "IC5") (pin "7") (pinfunction "QH_7") (pintype "tri_state"))
      (node (ref "R10") (pin "1") (pinfunction "1_1") (pintype "passive"))
    )
    (net (code "65") (name "Net-(IC2-O1)") (class "Default")
      (node (ref "IC2") (pin "18") (pinfunction "O1_18") (pintype "open_collector"))
      (node (ref "JP1") (pin "1") (pinfunction "1_1") (pintype "passive"))
      (node (ref "Q1") (pin "3") (pinfunction "D_3") (pintype "passive"))
    )
    (net (code "66") (name "Net-(IC2-O2)") (class "Default")
      (node (ref "IC2") (pin "17") (pinfunction "O2_17") (pintype "open_collector"))
      (node (ref "JP1") (pin "2") (pinfunction "2_2") (pintype "passive"))
      (node (ref "Q2") (pin "3") (pinfunction "D_3") (pintype "passive"))
    )
    (net (code "67") (name "Net-(IC2-O3)") (class "Default")
      (node (ref "IC2") (pin "16") (pinfunction "O3_16") (pintype "open_collector"))
      (node (ref "JP1") (pin "3") (pinfunction "3_3") (pintype "passive"))
      (node (ref "Q3") (pin "3") (pinfunction "D_3") (pintype "passive"))
    )
    (net (code "68") (name "Net-(IC2-O4)") (class "Default")
      (node (ref "IC2") (pin "15") (pinfunction "O4_15") (pintype "open_collector"))
      (node (ref "JP1") (pin "4") (pinfunction "4_4") (pintype "passive"))
      (node (ref "Q4") (pin "3") (pinfunction "D_3") (pintype "passive"))
    )
    (net (code "69") (name "Net-(IC2-O5)") (class "Default")
      (node (ref "IC2") (pin "14") (pinfunction "O5_14") (pintype "open_collector"))
      (node (ref "JP1") (pin "5") (pinfunction "5_5") (pintype "passive"))
      (node (ref "Q5") (pin "3") (pinfunction "D_3") (pintype "passive"))
    )
    (net (code "70") (name "Net-(IC2-O6)") (class "Default")
      (node (ref "IC2") (pin "13") (pinfunction "O6_13") (pintype "open_collector"))
      (node (ref "JP1") (pin "6") (pinfunction "6_6") (pintype "passive"))
      (node (ref "Q6") (pin "3") (pinfunction "D_3") (pintype "passive"))
    )
    (net (code "71") (name "Net-(IC2-O7)") (class "Default")
      (node (ref "IC2") (pin "12") (pinfunction "O7_12") (pintype "open_collector"))
      (node (ref "JP1") (pin "7") (pinfunction "7_7") (pintype "passive"))
      (node (ref "Q7") (pin "3") (pinfunction "D_3") (pintype "passive"))
    )
    (net (code "72") (name "Net-(IC2-O8)") (class "Default")
      (node (ref "IC2") (pin "11") (pinfunction "O8_11") (pintype "open_collector"))
      (node (ref "JP1") (pin "8") (pinfunction "8_8") (pintype "passive"))
      (node (ref "Q8") (pin "3") (pinfunction "D_3") (pintype "passive"))
    )
    (net (code "73") (name "Net-(IC3A-QA)") (class "Default")
      (node (ref "IC3") (pin "15") (pinfunction "QA_15") (pintype "tri_state"))
      (node (ref "IC8") (pin "1") (pinfunction "I1_1") (pintype "input"))
      (node (ref "R11") (pin "1") (pinfunction "1_1") (pintype "passive"))
    )
    (net (code "74") (name "Net-(IC3A-QB)") (class "Default")
      (node (ref "IC3") (pin "1") (pinfunction "QB_1") (pintype "tri_state"))
      (node (ref "IC8") (pin "2") (pinfunction "I2_2") (pintype "input"))
      (node (ref "R12") (pin "1") (pinfunction "1_1") (pintype "passive"))
    )
    (net (code "75") (name "Net-(IC3A-QC)") (class "Default")
      (node (ref "IC3") (pin "2") (pinfunction "QC_2") (pintype "tri_state"))
      (node (ref "IC8") (pin "3") (pinfunction "I3_3") (pintype "input"))
      (node (ref "R13") (pin "1") (pinfunction "1_1") (pintype "passive"))
    )
    (net (code "76") (name "Net-(IC3A-QD)") (class "Default")
      (node (ref "IC3") (pin "3") (pinfunction "QD_3") (pintype "tri_state"))
      (node (ref "IC8") (pin "4") (pinfunction "I4_4") (pintype "input"))
      (node (ref "R14") (pin "1") (pinfunction "1_1") (pintype "passive"))
    )
    (net (code "77") (name "Net-(IC3A-QE)") (class "Default")
      (node (ref "IC3") (pin "4") (pinfunction "QE_4") (pintype "tri_state"))
      (node (ref "IC8") (pin "5") (pinfunction "I5_5") (pintype "input"))
      (node (ref "R15") (pin "1") (pinfunction "1_1") (pintype "passive"))
    )
    (net (code "78") (name "Net-(IC3A-QF)") (class "Default")
      (node (ref "IC3") (pin "5") (pinfunction "QF_5") (pintype "tri_state"))
      (node (ref "IC8") (pin "6") (pinfunction "I6_6") (pintype "input"))
      (node (ref "R16") (pin "1") (pinfunction "1_1") (pintype "passive"))
    )
    (net (code "79") (name "Net-(IC3A-QG)") (class "Default")
      (node (ref "IC3") (pin "6") (pinfunction "QG_6") (pintype "tri_state"))
      (node (ref "IC8") (pin "7") (pinfunction "I7_7") (pintype "input"))
      (node (ref "R17") (pin "1") (pinfunction "1_1") (pintype "passive"))
    )
    (net (code "80") (name "Net-(IC3A-QH)") (class "Default")
      (node (ref "IC3") (pin "7") (pinfunction "QH_7") (pintype "tri_state"))
      (node (ref "IC8") (pin "8") (pinfunction "I8_8") (pintype "input"))
      (node (ref "R18") (pin "1") (pinfunction "1_1") (pintype "passive"))
    )
    (net (code "81") (name "Net-(IC4A-A)") (class "Default")
      (node (ref "IC4") (pin "2") (pinfunction "A_2") (pintype "input"))
      (node (ref "RN1") (pin "9") (pinfunction "2_9") (pintype "passive"))
    )
    (net (code "82") (name "Net-(IC4A-B)") (class "Default")
      (node (ref "IC4") (pin "3") (pinfunction "B_3") (pintype "input"))
      (node (ref "RN1") (pin "10") (pinfunction "2_10") (pintype "passive"))
    )
    (net (code "83") (name "Net-(IC4A-C)") (class "Default")
      (node (ref "IC4") (pin "4") (pinfunction "C_4") (pintype "input"))
      (node (ref "RN1") (pin "11") (pinfunction "2_11") (pintype "passive"))
    )
    (net (code "84") (name "Net-(IC4A-D)") (class "Default")
      (node (ref "IC4") (pin "5") (pinfunction "D_5") (pintype "input"))
      (node (ref "RN1") (pin "12") (pinfunction "2_12") (pintype "passive"))
    )
    (net (code "85") (name "Net-(IC4A-E)") (class "Default")
      (node (ref "IC4") (pin "10") (pinfunction "E_10") (pintype "input"))
      (node (ref "RN1") (pin "13") (pinfunction "2_13") (pintype "passive"))
    )
    (net (code "86") (name "Net-(IC4A-F)") (class "Default")
      (node (ref "IC4") (pin "11") (pinfunction "F_11") (pintype "input"))
      (node (ref "RN1") (pin "14") (pinfunction "2_14") (pintype "passive"))
    )
    (net (code "87") (name "Net-(IC4A-G)") (class "Default")
      (node (ref "IC4") (pin "12") (pinfunction "G_12") (pintype "input"))
      (node (ref "RN1") (pin "15") (pinfunction "2_15") (pintype "passive"))
    )
    (net (code "88") (name "Net-(IC4A-H)") (class "Default")
      (node (ref "IC4") (pin "14") (pinfunction "H_14") (pintype "input"))
      (node (ref "RN1") (pin "16") (pinfunction "2_16") (pintype "passive"))
    )
    (net (code "89") (name "Net-(IC6A--IN)") (class "Default")
      (node (ref "IC6") (pin "13") (pinfunction "-IN_13") (pintype "input"))
      (node (ref "IC6") (pin "2") (pinfunction "-IN_2") (pintype "input"))
      (node (ref "IC6") (pin "6") (pinfunction "-IN_6") (pintype "input"))
      (node (ref "IC6") (pin "9") (pinfunction "-IN_9") (pintype "input"))
      (node (ref "IC9") (pin "13") (pinfunction "-IN_13") (pintype "input"))
      (node (ref "IC9") (pin "2") (pinfunction "-IN_2") (pintype "input"))
      (node (ref "IC9") (pin "6") (pinfunction "-IN_6") (pintype "input"))
      (node (ref "IC9") (pin "9") (pinfunction "-IN_9") (pintype "input"))
      (node (ref "R1") (pin "1") (pinfunction "1_1") (pintype "passive"))
      (node (ref "R2") (pin "2") (pinfunction "2_2") (pintype "passive"))
    )
    (net (code "90") (name "Net-(IC6A-OUT)") (class "Default")
      (node (ref "IC6") (pin "1") (pinfunction "OUT_1") (pintype "output"))
      (node (ref "JP15") (pin "3") (pinfunction "3_3") (pintype "passive"))
      (node (ref "JP5") (pin "3") (pinfunction "3_3") (pintype "passive"))
      (node (ref "U$5") (pin "5") (pinfunction "O_5") (pintype "output"))
    )
    (net (code "91") (name "Net-(IC6B-OUT)") (class "Default")
      (node (ref "IC6") (pin "7") (pinfunction "OUT_7") (pintype "output"))
      (node (ref "JP15") (pin "1") (pinfunction "1_1") (pintype "passive"))
      (node (ref "JP5") (pin "1") (pinfunction "1_1") (pintype "passive"))
      (node (ref "U$4") (pin "7") (pinfunction "O_7") (pintype "output"))
    )
    (net (code "92") (name "Net-(IC6C-OUT)") (class "Default")
      (node (ref "IC6") (pin "8") (pinfunction "OUT_8") (pintype "output"))
      (node (ref "JP15") (pin "2") (pinfunction "2_2") (pintype "passive"))
      (node (ref "JP5") (pin "2") (pinfunction "2_2") (pintype "passive"))
      (node (ref "U$4") (pin "5") (pinfunction "O_5") (pintype "output"))
    )
    (net (code "93") (name "Net-(IC6D-OUT)") (class "Default")
      (node (ref "IC6") (pin "14") (pinfunction "OUT_14") (pintype "output"))
      (node (ref "JP15") (pin "4") (pinfunction "4_4") (pintype "passive"))
      (node (ref "JP5") (pin "4") (pinfunction "4_4") (pintype "passive"))
      (node (ref "U$5") (pin "7") (pinfunction "O_7") (pintype "output"))
    )
    (net (code "94") (name "Net-(IC8-CD+)") (class "Default")
      (node (ref "IC8") (pin "10") (pinfunction "CD+_10") (pintype "passive"))
      (node (ref "SJ10") (pin "1") (pinfunction "1_1") (pintype "passive"))
      (node (ref "SJ11") (pin "1") (pinfunction "1_1") (pintype "passive"))
      (node (ref "SJ12") (pin "1") (pinfunction "1_1") (pintype "passive"))
    )
    (net (code "95") (name "Net-(IC8-GND)") (class "Default")
      (node (ref "IC8") (pin "9") (pinfunction "GND_9") (pintype "power_in"))
      (node (ref "SJ7") (pin "1") (pinfunction "1_1") (pintype "passive"))
      (node (ref "SJ8") (pin "1") (pinfunction "1_1") (pintype "passive"))
      (node (ref "SJ9") (pin "1") (pinfunction "1_1") (pintype "passive"))
    )
    (net (code "96") (name "Net-(IC8-O1)") (class "Default")
      (node (ref "IC8") (pin "18") (pinfunction "O1_18") (pintype "open_collector"))
      (node (ref "JP6") (pin "1") (pinfunction "1_1") (pintype "passive"))
      (node (ref "Q9") (pin "3") (pinfunction "D_3") (pintype "passive"))
    )
    (net (code "97") (name "Net-(IC8-O2)") (class "Default")
      (node (ref "IC8") (pin "17") (pinfunction "O2_17") (pintype "open_collector"))
      (node (ref "JP6") (pin "2") (pinfunction "2_2") (pintype "passive"))
      (node (ref "Q10") (pin "3") (pinfunction "D_3") (pintype "passive"))
    )
    (net (code "98") (name "Net-(IC8-O3)") (class "Default")
      (node (ref "IC8") (pin "16") (pinfunction "O3_16") (pintype "open_collector"))
      (node (ref "JP6") (pin "3") (pinfunction "3_3") (pintype "passive"))
      (node (ref "Q11") (pin "3") (pinfunction "D_3") (pintype "passive"))
    )
    (net (code "99") (name "Net-(IC8-O4)") (class "Default")
      (node (ref "IC8") (pin "15") (pinfunction "O4_15") (pintype "open_collector"))
      (node (ref "JP6") (pin "4") (pinfunction "4_4") (pintype "passive"))
      (node (ref "Q12") (pin "3") (pinfunction "D_3") (pintype "passive"))
    )
    (net (code "100") (name "Net-(IC8-O5)") (class "Default")
      (node (ref "IC8") (pin "14") (pinfunction "O5_14") (pintype "open_collector"))
      (node (ref "JP6") (pin "5") (pinfunction "5_5") (pintype "passive"))
      (node (ref "Q13") (pin "3") (pinfunction "D_3") (pintype "passive"))
    )
    (net (code "101") (name "Net-(IC8-O6)") (class "Default")
      (node (ref "IC8") (pin "13") (pinfunction "O6_13") (pintype "open_collector"))
      (node (ref "JP6") (pin "6") (pinfunction "6_6") (pintype "passive"))
      (node (ref "Q14") (pin "3") (pinfunction "D_3") (pintype "passive"))
    )
    (net (code "102") (name "Net-(IC8-O7)") (class "Default")
      (node (ref "IC8") (pin "12") (pinfunction "O7_12") (pintype "open_collector"))
      (node (ref "JP6") (pin "7") (pinfunction "7_7") (pintype "passive"))
      (node (ref "Q15") (pin "3") (pinfunction "D_3") (pintype "passive"))
    )
    (net (code "103") (name "Net-(IC8-O8)") (class "Default")
      (node (ref "IC8") (pin "11") (pinfunction "O8_11") (pintype "open_collector"))
      (node (ref "JP6") (pin "8") (pinfunction "8_8") (pintype "passive"))
      (node (ref "Q16") (pin "3") (pinfunction "D_3") (pintype "passive"))
    )
    (net (code "104") (name "Net-(IC9A-OUT)") (class "Default")
      (node (ref "IC9") (pin "1") (pinfunction "OUT_1") (pintype "output"))
      (node (ref "JP15") (pin "9") (pinfunction "9_9") (pintype "passive"))
      (node (ref "JP5") (pin "7") (pinfunction "7_7") (pintype "passive"))
      (node (ref "U$3") (pin "5") (pinfunction "O_5") (pintype "output"))
    )
    (net (code "105") (name "Net-(IC9B-OUT)") (class "Default")
      (node (ref "IC9") (pin "7") (pinfunction "OUT_7") (pintype "output"))
      (node (ref "JP15") (pin "7") (pinfunction "7_7") (pintype "passive"))
      (node (ref "JP5") (pin "5") (pinfunction "5_5") (pintype "passive"))
      (node (ref "U$2") (pin "7") (pinfunction "O_7") (pintype "output"))
    )
    (net (code "106") (name "Net-(IC9C-OUT)") (class "Default")
      (node (ref "IC9") (pin "8") (pinfunction "OUT_8") (pintype "output"))
      (node (ref "JP15") (pin "8") (pinfunction "8_8") (pintype "passive"))
      (node (ref "JP5") (pin "6") (pinfunction "6_6") (pintype "passive"))
      (node (ref "U$2") (pin "5") (pinfunction "O_5") (pintype "output"))
    )
    (net (code "107") (name "Net-(IC9D-OUT)") (class "Default")
      (node (ref "IC9") (pin "14") (pinfunction "OUT_14") (pintype "output"))
      (node (ref "JP15") (pin "10") (pinfunction "10_10") (pintype "passive"))
      (node (ref "JP5") (pin "8") (pinfunction "8_8") (pintype "passive"))
      (node (ref "U$3") (pin "7") (pinfunction "O_7") (pintype "output"))
    )
    (net (code "108") (name "Net-(J1-Pad4)") (class "Default")
      (node (ref "J1") (pin "4") (pinfunction "4_4") (pintype "passive"))
      (node (ref "J2") (pin "4") (pinfunction "4_4") (pintype "passive"))
    )
    (net (code "109") (name "Net-(J1-Pad5)") (class "Default")
      (node (ref "J1") (pin "5") (pinfunction "5_5") (pintype "passive"))
      (node (ref "J2") (pin "5") (pinfunction "5_5") (pintype "passive"))
    )
    (net (code "110") (name "Net-(J1-Pad8)") (class "Default")
      (node (ref "J1") (pin "8") (pinfunction "8_8") (pintype "passive"))
      (node (ref "J2") (pin "8") (pinfunction "8_8") (pintype "passive"))
      (node (ref "R40") (pin "1") (pinfunction "1_1") (pintype "passive"))
    )
    (net (code "111") (name "Net-(JP4-Pad3)") (class "Default")
      (node (ref "JP4") (pin "3") (pinfunction "3_3") (pintype "passive"))
      (node (ref "R40") (pin "2") (pinfunction "2_2") (pintype "passive"))
    )
    (net (code "112") (name "Net-(JP13-Pad1)") (class "Default")
      (node (ref "JP13") (pin "1") (pinfunction "1_1") (pintype "passive"))
      (node (ref "JP3") (pin "1") (pinfunction "1_1") (pintype "passive"))
      (node (ref "RN4") (pin "1") (pinfunction "1_1") (pintype "passive"))
      (node (ref "RN5") (pin "9") (pinfunction "9_9") (pintype "passive"))
    )
    (net (code "113") (name "Net-(JP14-Pad1)") (class "Default")
      (node (ref "JP14") (pin "1") (pinfunction "1_1") (pintype "passive"))
      (node (ref "JP2") (pin "1") (pinfunction "1_1") (pintype "passive"))
      (node (ref "RN1") (pin "1") (pinfunction "1_1") (pintype "passive"))
      (node (ref "RN2") (pin "9") (pinfunction "9_9") (pintype "passive"))
    )
    (net (code "114") (name "Net-(Q1-G)") (class "Default")
      (node (ref "Q1") (pin "1") (pinfunction "G_1") (pintype "passive"))
      (node (ref "R3") (pin "2") (pinfunction "2_2") (pintype "passive"))
    )
    (net (code "115") (name "Net-(Q2-G)") (class "Default")
      (node (ref "Q2") (pin "1") (pinfunction "G_1") (pintype "passive"))
      (node (ref "R4") (pin "2") (pinfunction "2_2") (pintype "passive"))
    )
    (net (code "116") (name "Net-(Q3-G)") (class "Default")
      (node (ref "Q3") (pin "1") (pinfunction "G_1") (pintype "passive"))
      (node (ref "R5") (pin "2") (pinfunction "2_2") (pintype "passive"))
    )
    (net (code "117") (name "Net-(Q4-G)") (class "Default")
      (node (ref "Q4") (pin "1") (pinfunction "G_1") (pintype "passive"))
      (node (ref "R6") (pin "2") (pinfunction "2_2") (pintype "passive"))
    )
    (net (code "118") (name "Net-(Q5-G)") (class "Default")
      (node (ref "Q5") (pin "1") (pinfunction "G_1") (pintype "passive"))
      (node (ref "R7") (pin "2") (pinfunction "2_2") (pintype "passive"))
    )
    (net (code "119") (name "Net-(Q6-G)") (class "Default")
      (node (ref "Q6") (pin "1") (pinfunction "G_1") (pintype "passive"))
      (node (ref "R8") (pin "2") (pinfunction "2_2") (pintype "passive"))
    )
    (net (code "120") (name "Net-(Q7-G)") (class "Default")
      (node (ref "Q7") (pin "1") (pinfunction "G_1") (pintype "passive"))
      (node (ref "R9") (pin "2") (pinfunction "2_2") (pintype "passive"))
    )
    (net (code "121") (name "Net-(Q8-G)") (class "Default")
      (node (ref "Q8") (pin "1") (pinfunction "G_1") (pintype "passive"))
      (node (ref "R10") (pin "2") (pinfunction "2_2") (pintype "passive"))
    )
    (net (code "122") (name "Net-(Q9-G)") (class "Default")
      (node (ref "Q9") (pin "1") (pinfunction "G_1") (pintype "passive"))
      (node (ref "R11") (pin "2") (pinfunction "2_2") (pintype "passive"))
    )
    (net (code "123") (name "Net-(Q10-G)") (class "Default")
      (node (ref "Q10") (pin "1") (pinfunction "G_1") (pintype "passive"))
      (node (ref "R12") (pin "2") (pinfunction "2_2") (pintype "passive"))
    )
    (net (code "124") (name "Net-(Q11-G)") (class "Default")
      (node (ref "Q11") (pin "1") (pinfunction "G_1") (pintype "passive"))
      (node (ref "R13") (pin "2") (pinfunction "2_2") (pintype "passive"))
    )
    (net (code "125") (name "Net-(Q12-G)") (class "Default")
      (node (ref "Q12") (pin "1") (pinfunction "G_1") (pintype "passive"))
      (node (ref "R14") (pin "2") (pinfunction "2_2") (pintype "passive"))
    )
    (net (code "126") (name "Net-(Q13-G)") (class "Default")
      (node (ref "Q13") (pin "1") (pinfunction "G_1") (pintype "passive"))
      (node (ref "R15") (pin "2") (pinfunction "2_2") (pintype "passive"))
    )
    (net (code "127") (name "Net-(Q14-G)") (class "Default")
      (node (ref "Q14") (pin "1") (pinfunction "G_1") (pintype "passive"))
      (node (ref "R16") (pin "2") (pinfunction "2_2") (pintype "passive"))
    )
    (net (code "128") (name "Net-(Q15-G)") (class "Default")
      (node (ref "Q15") (pin "1") (pinfunction "G_1") (pintype "passive"))
      (node (ref "R17") (pin "2") (pinfunction "2_2") (pintype "passive"))
    )
    (net (code "129") (name "Net-(Q16-G)") (class "Default")
      (node (ref "Q16") (pin "1") (pinfunction "G_1") (pintype "passive"))
      (node (ref "R18") (pin "2") (pinfunction "2_2") (pintype "passive"))
    )
    (net (code "130") (name "Net-(RN1B-1)") (class "Default")
      (node (ref "JP14") (pin "2") (pinfunction "2_2") (pintype "passive"))
      (node (ref "JP2") (pin "2") (pinfunction "2_2") (pintype "passive"))
      (node (ref "RN1") (pin "2") (pinfunction "1_2") (pintype "passive"))
      (node (ref "RN2") (pin "8") (pinfunction "8_8") (pintype "passive"))
    )
    (net (code "131") (name "Net-(RN1C-1)") (class "Default")
      (node (ref "JP14") (pin "3") (pinfunction "3_3") (pintype "passive"))
      (node (ref "JP2") (pin "3") (pinfunction "3_3") (pintype "passive"))
      (node (ref "RN1") (pin "3") (pinfunction "1_3") (pintype "passive"))
      (node (ref "RN2") (pin "7") (pinfunction "7_7") (pintype "passive"))
    )
    (net (code "132") (name "Net-(RN1D-1)") (class "Default")
      (node (ref "JP14") (pin "4") (pinfunction "4_4") (pintype "passive"))
      (node (ref "JP2") (pin "4") (pinfunction "4_4") (pintype "passive"))
      (node (ref "RN1") (pin "4") (pinfunction "1_4") (pintype "passive"))
      (node (ref "RN2") (pin "6") (pinfunction "6_6") (pintype "passive"))
    )
    (net (code "133") (name "Net-(RN1E-1)") (class "Default")
      (node (ref "JP14") (pin "7") (pinfunction "7_7") (pintype "passive"))
      (node (ref "JP2") (pin "5") (pinfunction "5_5") (pintype "passive"))
      (node (ref "RN1") (pin "5") (pinfunction "1_5") (pintype "passive"))
      (node (ref "RN2") (pin "5") (pinfunction "5_5") (pintype "passive"))
    )
    (net (code "134") (name "Net-(RN1F-1)") (class "Default")
      (node (ref "JP14") (pin "8") (pinfunction "8_8") (pintype "passive"))
      (node (ref "JP2") (pin "6") (pinfunction "6_6") (pintype "passive"))
      (node (ref "RN1") (pin "6") (pinfunction "1_6") (pintype "passive"))
      (node (ref "RN2") (pin "4") (pinfunction "4_4") (pintype "passive"))
    )
    (net (code "135") (name "Net-(RN1G-1)") (class "Default")
      (node (ref "JP14") (pin "9") (pinfunction "9_9") (pintype "passive"))
      (node (ref "JP2") (pin "7") (pinfunction "7_7") (pintype "passive"))
      (node (ref "RN1") (pin "7") (pinfunction "1_7") (pintype "passive"))
      (node (ref "RN2") (pin "3") (pinfunction "3_3") (pintype "passive"))
    )
    (net (code "136") (name "Net-(RN1H-1)") (class "Default")
      (node (ref "JP14") (pin "10") (pinfunction "10_10") (pintype "passive"))
      (node (ref "JP2") (pin "8") (pinfunction "8_8") (pintype "passive"))
      (node (ref "RN1") (pin "8") (pinfunction "1_8") (pintype "passive"))
      (node (ref "RN2") (pin "2") (pinfunction "2_2") (pintype "passive"))
    )
    (net (code "137") (name "Net-(RN4B-1)") (class "Default")
      (node (ref "JP13") (pin "2") (pinfunction "2_2") (pintype "passive"))
      (node (ref "JP3") (pin "2") (pinfunction "2_2") (pintype "passive"))
      (node (ref "RN4") (pin "2") (pinfunction "1_2") (pintype "passive"))
      (node (ref "RN5") (pin "8") (pinfunction "8_8") (pintype "passive"))
    )
    (net (code "138") (name "Net-(RN4C-1)") (class "Default")
      (node (ref "JP13") (pin "3") (pinfunction "3_3") (pintype "passive"))
      (node (ref "JP3") (pin "3") (pinfunction "3_3") (pintype "passive"))
      (node (ref "RN4") (pin "3") (pinfunction "1_3") (pintype "passive"))
      (node (ref "RN5") (pin "7") (pinfunction "7_7") (pintype "passive"))
    )
    (net (code "139") (name "Net-(RN4D-1)") (class "Default")
      (node (ref "JP13") (pin "4") (pinfunction "4_4") (pintype "passive"))
      (node (ref "JP3") (pin "4") (pinfunction "4_4") (pintype "passive"))
      (node (ref "RN4") (pin "4") (pinfunction "1_4") (pintype "passive"))
      (node (ref "RN5") (pin "6") (pinfunction "6_6") (pintype "passive"))
    )
    (net (code "140") (name "Net-(RN4E-1)") (class "Default")
      (node (ref "JP13") (pin "7") (pinfunction "7_7") (pintype "passive"))
      (node (ref "JP3") (pin "5") (pinfunction "5_5") (pintype "passive"))
      (node (ref "RN4") (pin "5") (pinfunction "1_5") (pintype "passive"))
      (node (ref "RN5") (pin "5") (pinfunction "5_5") (pintype "passive"))
    )
    (net (code "141") (name "Net-(RN4F-1)") (class "Default")
      (node (ref "JP13") (pin "8") (pinfunction "8_8") (pintype "passive"))
      (node (ref "JP3") (pin "6") (pinfunction "6_6") (pintype "passive"))
      (node (ref "RN4") (pin "6") (pinfunction "1_6") (pintype "passive"))
      (node (ref "RN5") (pin "4") (pinfunction "4_4") (pintype "passive"))
    )
    (net (code "142") (name "Net-(RN4G-1)") (class "Default")
      (node (ref "JP13") (pin "9") (pinfunction "9_9") (pintype "passive"))
      (node (ref "JP3") (pin "7") (pinfunction "7_7") (pintype "passive"))
      (node (ref "RN4") (pin "7") (pinfunction "1_7") (pintype "passive"))
      (node (ref "RN5") (pin "3") (pinfunction "3_3") (pintype "passive"))
    )
    (net (code "143") (name "Net-(RN4H-1)") (class "Default")
      (node (ref "JP13") (pin "10") (pinfunction "10_10") (pintype "passive"))
      (node (ref "JP3") (pin "8") (pinfunction "8_8") (pintype "passive"))
      (node (ref "RN4") (pin "8") (pinfunction "1_8") (pintype "passive"))
      (node (ref "RN5") (pin "2") (pinfunction "2_2") (pintype "passive"))
    )
    (net (code "144") (name "OLAT") (class "Default")
      (node (ref "IC3") (pin "12") (pinfunction "RCK_12") (pintype "input"))
      (node (ref "IC5") (pin "12") (pinfunction "RCK_12") (pintype "input"))
      (node (ref "R21") (pin "1") (pinfunction "1_1") (pintype "passive"))
      (node (ref "U$1") (pin "PA8") (pinfunction "PA8_PA8") (pintype "bidirectional"))
    )
    (net (code "145") (name "SCK") (class "Default")
      (node (ref "IC1") (pin "7") (pinfunction "CLK_7") (pintype "input"))
      (node (ref "IC3") (pin "11") (pinfunction "SCK_11") (pintype "input"))
      (node (ref "IC4") (pin "7") (pinfunction "CLK_7") (pintype "input"))
      (node (ref "IC5") (pin "11") (pinfunction "SCK_11") (pintype "input"))
      (node (ref "R19") (pin "1") (pinfunction "1_1") (pintype "passive"))
      (node (ref "U$1") (pin "PB3") (pinfunction "PB3_PB3") (pintype "bidirectional"))
    )
    (net (code "146") (name "SLNK1") (class "Default")
      (node (ref "IC3") (pin "14") (pinfunction "SER_14") (pintype "input"))
      (node (ref "IC5") (pin "9") (pinfunction "QH*_9") (pintype "tri_state"))
    )
    (net (code "147") (name "unconnected-(H1-MOUNT-PadB3,3)") (class "Default")
      (node (ref "H1") (pin "B3,3") (pinfunction "MOUNT_B3,3") (pintype "passive"))
    )
    (net (code "148") (name "unconnected-(H2-MOUNT-PadB3,3)") (class "Default")
      (node (ref "H2") (pin "B3,3") (pinfunction "MOUNT_B3,3") (pintype "passive"))
    )
    (net (code "149") (name "unconnected-(H3-MOUNT-PadB3,3)") (class "Default")
      (node (ref "H3") (pin "B3,3") (pinfunction "MOUNT_B3,3") (pintype "passive"))
    )
    (net (code "150") (name "unconnected-(H4-MOUNT-PadB3,3)") (class "Default")
      (node (ref "H4") (pin "B3,3") (pinfunction "MOUNT_B3,3") (pintype "passive"))
    )
    (net (code "151") (name "unconnected-(IC3A-QH*-Pad9)") (class "Default")
      (node (ref "IC3") (pin "9") (pinfunction "QH*_9") (pintype "tri_state"))
    )
    (net (code "152") (name "unconnected-(IC7-RS-Pad8)") (class "Default")
      (node (ref "IC7") (pin "8") (pinfunction "RS_8") (pintype "input"))
    )
    (net (code "153") (name "unconnected-(IC7-VREF-Pad5)") (class "Default")
      (node (ref "IC7") (pin "5") (pinfunction "VREF_5") (pintype "output"))
    )
    (net (code "154") (name "unconnected-(J3-Pad2)") (class "Default")
      (node (ref "J3") (pin "2") (pinfunction "2_2") (pintype "passive"))
    )
    (net (code "155") (name "unconnected-(JP7-Pad1)") (class "Default")
      (node (ref "JP7") (pin "1") (pinfunction "1_1") (pintype "passive"))
    )
    (net (code "156") (name "unconnected-(JP7-Pad2)") (class "Default")
      (node (ref "JP7") (pin "2") (pinfunction "2_2") (pintype "passive"))
    )
    (net (code "157") (name "unconnected-(JP7-Pad3)") (class "Default")
      (node (ref "JP7") (pin "3") (pinfunction "3_3") (pintype "passive"))
    )
    (net (code "158") (name "unconnected-(JP7-Pad4)") (class "Default")
      (node (ref "JP7") (pin "4") (pinfunction "4_4") (pintype "passive"))
    )
    (net (code "159") (name "unconnected-(JP7-Pad5)") (class "Default")
      (node (ref "JP7") (pin "5") (pinfunction "5_5") (pintype "passive"))
    )
    (net (code "160") (name "unconnected-(JP7-Pad6)") (class "Default")
      (node (ref "JP7") (pin "6") (pinfunction "6_6") (pintype "passive"))
    )
    (net (code "161") (name "unconnected-(JP8-Pad1)") (class "Default")
      (node (ref "JP8") (pin "1") (pinfunction "1_1") (pintype "passive"))
    )
    (net (code "162") (name "unconnected-(JP8-Pad2)") (class "Default")
      (node (ref "JP8") (pin "2") (pinfunction "2_2") (pintype "passive"))
    )
    (net (code "163") (name "unconnected-(JP8-Pad3)") (class "Default")
      (node (ref "JP8") (pin "3") (pinfunction "3_3") (pintype "passive"))
    )
    (net (code "164") (name "unconnected-(JP8-Pad4)") (class "Default")
      (node (ref "JP8") (pin "4") (pinfunction "4_4") (pintype "passive"))
    )
    (net (code "165") (name "unconnected-(JP9-Pad1)") (class "Default")
      (node (ref "JP9") (pin "1") (pinfunction "1_1") (pintype "passive"))
    )
    (net (code "166") (name "unconnected-(JP9-Pad2)") (class "Default")
      (node (ref "JP9") (pin "2") (pinfunction "2_2") (pintype "passive"))
    )
    (net (code "167") (name "unconnected-(JP9-Pad3)") (class "Default")
      (node (ref "JP9") (pin "3") (pinfunction "3_3") (pintype "passive"))
    )
    (net (code "168") (name "unconnected-(JP9-Pad4)") (class "Default")
      (node (ref "JP9") (pin "4") (pinfunction "4_4") (pintype "passive"))
    )
    (net (code "169") (name "unconnected-(JP10-Pad1)") (class "Default")
      (node (ref "JP10") (pin "1") (pinfunction "1_1") (pintype "passive"))
    )
    (net (code "170") (name "unconnected-(JP10-Pad2)") (class "Default")
      (node (ref "JP10") (pin "2") (pinfunction "2_2") (pintype "passive"))
    )
    (net (code "171") (name "unconnected-(JP10-Pad3)") (class "Default")
      (node (ref "JP10") (pin "3") (pinfunction "3_3") (pintype "passive"))
    )
    (net (code "172") (name "unconnected-(JP10-Pad4)") (class "Default")
      (node (ref "JP10") (pin "4") (pinfunction "4_4") (pintype "passive"))
    )
    (net (code "173") (name "unconnected-(JP11-Pad1)") (class "Default")
      (node (ref "JP11") (pin "1") (pinfunction "1_1") (pintype "passive"))
    )
    (net (code "174") (name "unconnected-(JP11-Pad2)") (class "Default")
      (node (ref "JP11") (pin "2") (pinfunction "2_2") (pintype "passive"))
    )
    (net (code "175") (name "unconnected-(JP11-Pad3)") (class "Default")
      (node (ref "JP11") (pin "3") (pinfunction "3_3") (pintype "passive"))
    )
    (net (code "176") (name "unconnected-(JP11-Pad4)") (class "Default")
      (node (ref "JP11") (pin "4") (pinfunction "4_4") (pintype "passive"))
    )
    (net (code "177") (name "unconnected-(JP11-Pad5)") (class "Default")
      (node (ref "JP11") (pin "5") (pinfunction "5_5") (pintype "passive"))
    )
    (net (code "178") (name "unconnected-(JP11-Pad6)") (class "Default")
      (node (ref "JP11") (pin "6") (pinfunction "6_6") (pintype "passive"))
    )
    (net (code "179") (name "unconnected-(U$1-PadBOOT0)") (class "Default")
      (node (ref "U$1") (pin "BOOT0") (pinfunction "BOOT0_BOOT0") (pintype "bidirectional"))
    )
    (net (code "180") (name "unconnected-(U$1-PadIOREF2)") (class "Default")
      (node (ref "U$1") (pin "IOREF2") (pinfunction "IOREF2_IOREF2") (pintype "input"))
    )
    (net (code "181") (name "unconnected-(U$1-PadNC1-PF7)") (class "Default")
      (node (ref "U$1") (pin "NC1-PF7") (pinfunction "NC1-PF7_NC1-PF7") (pintype "bidirectional"))
    )
    (net (code "182") (name "unconnected-(U$1-PadNC2-PF6)") (class "Default")
      (node (ref "U$1") (pin "NC2-PF6") (pinfunction "NC2-PF6_NC2-PF6") (pintype "bidirectional"))
    )
    (net (code "183") (name "unconnected-(U$1-PadNC3)") (class "Default")
      (node (ref "U$1") (pin "NC3") (pinfunction "NC3_NC3") (pintype "no_connect"))
    )
    (net (code "184") (name "unconnected-(U$1-PadNC4)") (class "Default")
      (node (ref "U$1") (pin "NC4") (pinfunction "NC4_NC4") (pintype "no_connect"))
    )
    (net (code "185") (name "unconnected-(U$1-PadNC5-PD8)") (class "Default")
      (node (ref "U$1") (pin "NC5-PD8") (pinfunction "NC5-PD8_NC5-PD8") (pintype "bidirectional"))
    )
    (net (code "186") (name "unconnected-(U$1-PadNC6-PB11)") (class "Default")
      (node (ref "U$1") (pin "NC6-PB11") (pinfunction "NC6-PB11_NC6-PB11") (pintype "no_connect"))
    )
    (net (code "187") (name "unconnected-(U$1-PadNC7-PF5)") (class "Default")
      (node (ref "U$1") (pin "NC7-PF5") (pinfunction "NC7-PF5_NC7-PF5") (pintype "bidirectional"))
    )
    (net (code "188") (name "unconnected-(U$1-PadNC8-PF4)") (class "Default")
      (node (ref "U$1") (pin "NC8-PF4") (pinfunction "NC8-PF4_NC8-PF4") (pintype "bidirectional"))
    )
    (net (code "189") (name "unconnected-(U$1-PadNRESET)") (class "Default")
      (node (ref "U$1") (pin "NRESET") (pinfunction "NRESET_NRESET") (pintype "input"))
    )
    (net (code "190") (name "unconnected-(U$1-PadPA1)") (class "Default")
      (node (ref "U$1") (pin "PA1") (pinfunction "PA1_PA1") (pintype "bidirectional"))
    )
    (net (code "191") (name "unconnected-(U$1-PadPA2)") (class "Default")
      (node (ref "U$1") (pin "PA2") (pinfunction "PA2_PA2") (pintype "bidirectional"))
    )
    (net (code "192") (name "unconnected-(U$1-PadPA3)") (class "Default")
      (node (ref "U$1") (pin "PA3") (pinfunction "PA3_PA3") (pintype "bidirectional"))
    )
    (net (code "193") (name "unconnected-(U$1-PadPA5)") (class "Default")
      (node (ref "U$1") (pin "PA5") (pinfunction "PA5_PA5") (pintype "bidirectional"))
    )
    (net (code "194") (name "unconnected-(U$1-PadPA7)") (class "Default")
      (node (ref "U$1") (pin "PA7") (pinfunction "PA7_PA7") (pintype "bidirectional"))
    )
    (net (code "195") (name "unconnected-(U$1-PadPA9)") (class "Default")
      (node (ref "U$1") (pin "PA9") (pinfunction "PA9_PA9") (pintype "bidirectional"))
    )
    (net (code "196") (name "unconnected-(U$1-PadPA10)") (class "Default")
      (node (ref "U$1") (pin "PA10") (pinfunction "PA10_PA10") (pintype "bidirectional"))
    )
    (net (code "197") (name "unconnected-(U$1-PadPA11)") (class "Default")
      (node (ref "U$1") (pin "PA11") (pinfunction "PA11_PA11") (pintype "bidirectional"))
    )
    (net (code "198") (name "unconnected-(U$1-PadPA12)") (class "Default")
      (node (ref "U$1") (pin "PA12") (pinfunction "PA12_PA12") (pintype "bidirectional"))
    )
    (net (code "199") (name "unconnected-(U$1-PadPA13)") (class "Default")
      (node (ref "U$1") (pin "PA13") (pinfunction "PA13_PA13") (pintype "bidirectional"))
    )
    (net (code "200") (name "unconnected-(U$1-PadPA14)") (class "Default")
      (node (ref "U$1") (pin "PA14") (pinfunction "PA14_PA14") (pintype "bidirectional"))
    )
    (net (code "201") (name "unconnected-(U$1-PadPB0)") (class "Default")
      (node (ref "U$1") (pin "PB0") (pinfunction "PB0_PB0") (pintype "bidirectional"))
    )
    (net (code "202") (name "unconnected-(U$1-PadPB6)") (class "Default")
      (node (ref "U$1") (pin "PB6") (pinfunction "PB6_PB6") (pintype "bidirectional"))
    )
    (net (code "203") (name "unconnected-(U$1-PadPB7)") (class "Default")
      (node (ref "U$1") (pin "PB7") (pinfunction "PB7_PB7") (pintype "bidirectional"))
    )
    (net (code "204") (name "unconnected-(U$1-PadPB13)") (class "Default")
      (node (ref "U$1") (pin "PB13") (pinfunction "PB13_PB13") (pintype "bidirectional"))
    )
    (net (code "205") (name "unconnected-(U$1-PadPB14)") (class "Default")
      (node (ref "U$1") (pin "PB14") (pinfunction "PB14_PB14") (pintype "bidirectional"))
    )
    (net (code "206") (name "unconnected-(U$1-PadPC1)") (class "Default")
      (node (ref "U$1") (pin "PC1") (pinfunction "PC1_PC1") (pintype "bidirectional"))
    )
    (net (code "207") (name "unconnected-(U$1-PadPC4)") (class "Default")
      (node (ref "U$1") (pin "PC4") (pinfunction "PC4_PC4") (pintype "bidirectional"))
    )
    (net (code "208") (name "unconnected-(U$1-PadPC5)") (class "Default")
      (node (ref "U$1") (pin "PC5") (pinfunction "PC5_PC5") (pintype "bidirectional"))
    )
    (net (code "209") (name "unconnected-(U$1-PadPC6)") (class "Default")
      (node (ref "U$1") (pin "PC6") (pinfunction "PC6_PC6") (pintype "bidirectional"))
    )
    (net (code "210") (name "unconnected-(U$1-PadPC7)") (class "Default")
      (node (ref "U$1") (pin "PC7") (pinfunction "PC7_PC7") (pintype "bidirectional"))
    )
    (net (code "211") (name "unconnected-(U$1-PadPC8)") (class "Default")
      (node (ref "U$1") (pin "PC8") (pinfunction "PC8_PC8") (pintype "bidirectional"))
    )
    (net (code "212") (name "unconnected-(U$1-PadPC9)") (class "Default")
      (node (ref "U$1") (pin "PC9") (pinfunction "PC9_PC9") (pintype "bidirectional"))
    )
    (net (code "213") (name "unconnected-(U$1-PadPC13)") (class "Default")
      (node (ref "U$1") (pin "PC13") (pinfunction "PC13_PC13") (pintype "bidirectional"))
    )
    (net (code "214") (name "unconnected-(U$1-PadPC14)") (class "Default")
      (node (ref "U$1") (pin "PC14") (pinfunction "PC14_PC14") (pintype "bidirectional"))
    )
    (net (code "215") (name "unconnected-(U$1-PadPC15)") (class "Default")
      (node (ref "U$1") (pin "PC15") (pinfunction "PC15_PC15") (pintype "bidirectional"))
    )
    (net (code "216") (name "unconnected-(U$1-PadPF0-PH0)") (class "Default")
      (node (ref "U$1") (pin "PF0-PH0") (pinfunction "PF0-PH0_PF0-PH0") (pintype "bidirectional"))
    )
  )
)
